# R211.net
KiCad netlist of a schematic drawn in EAGLE
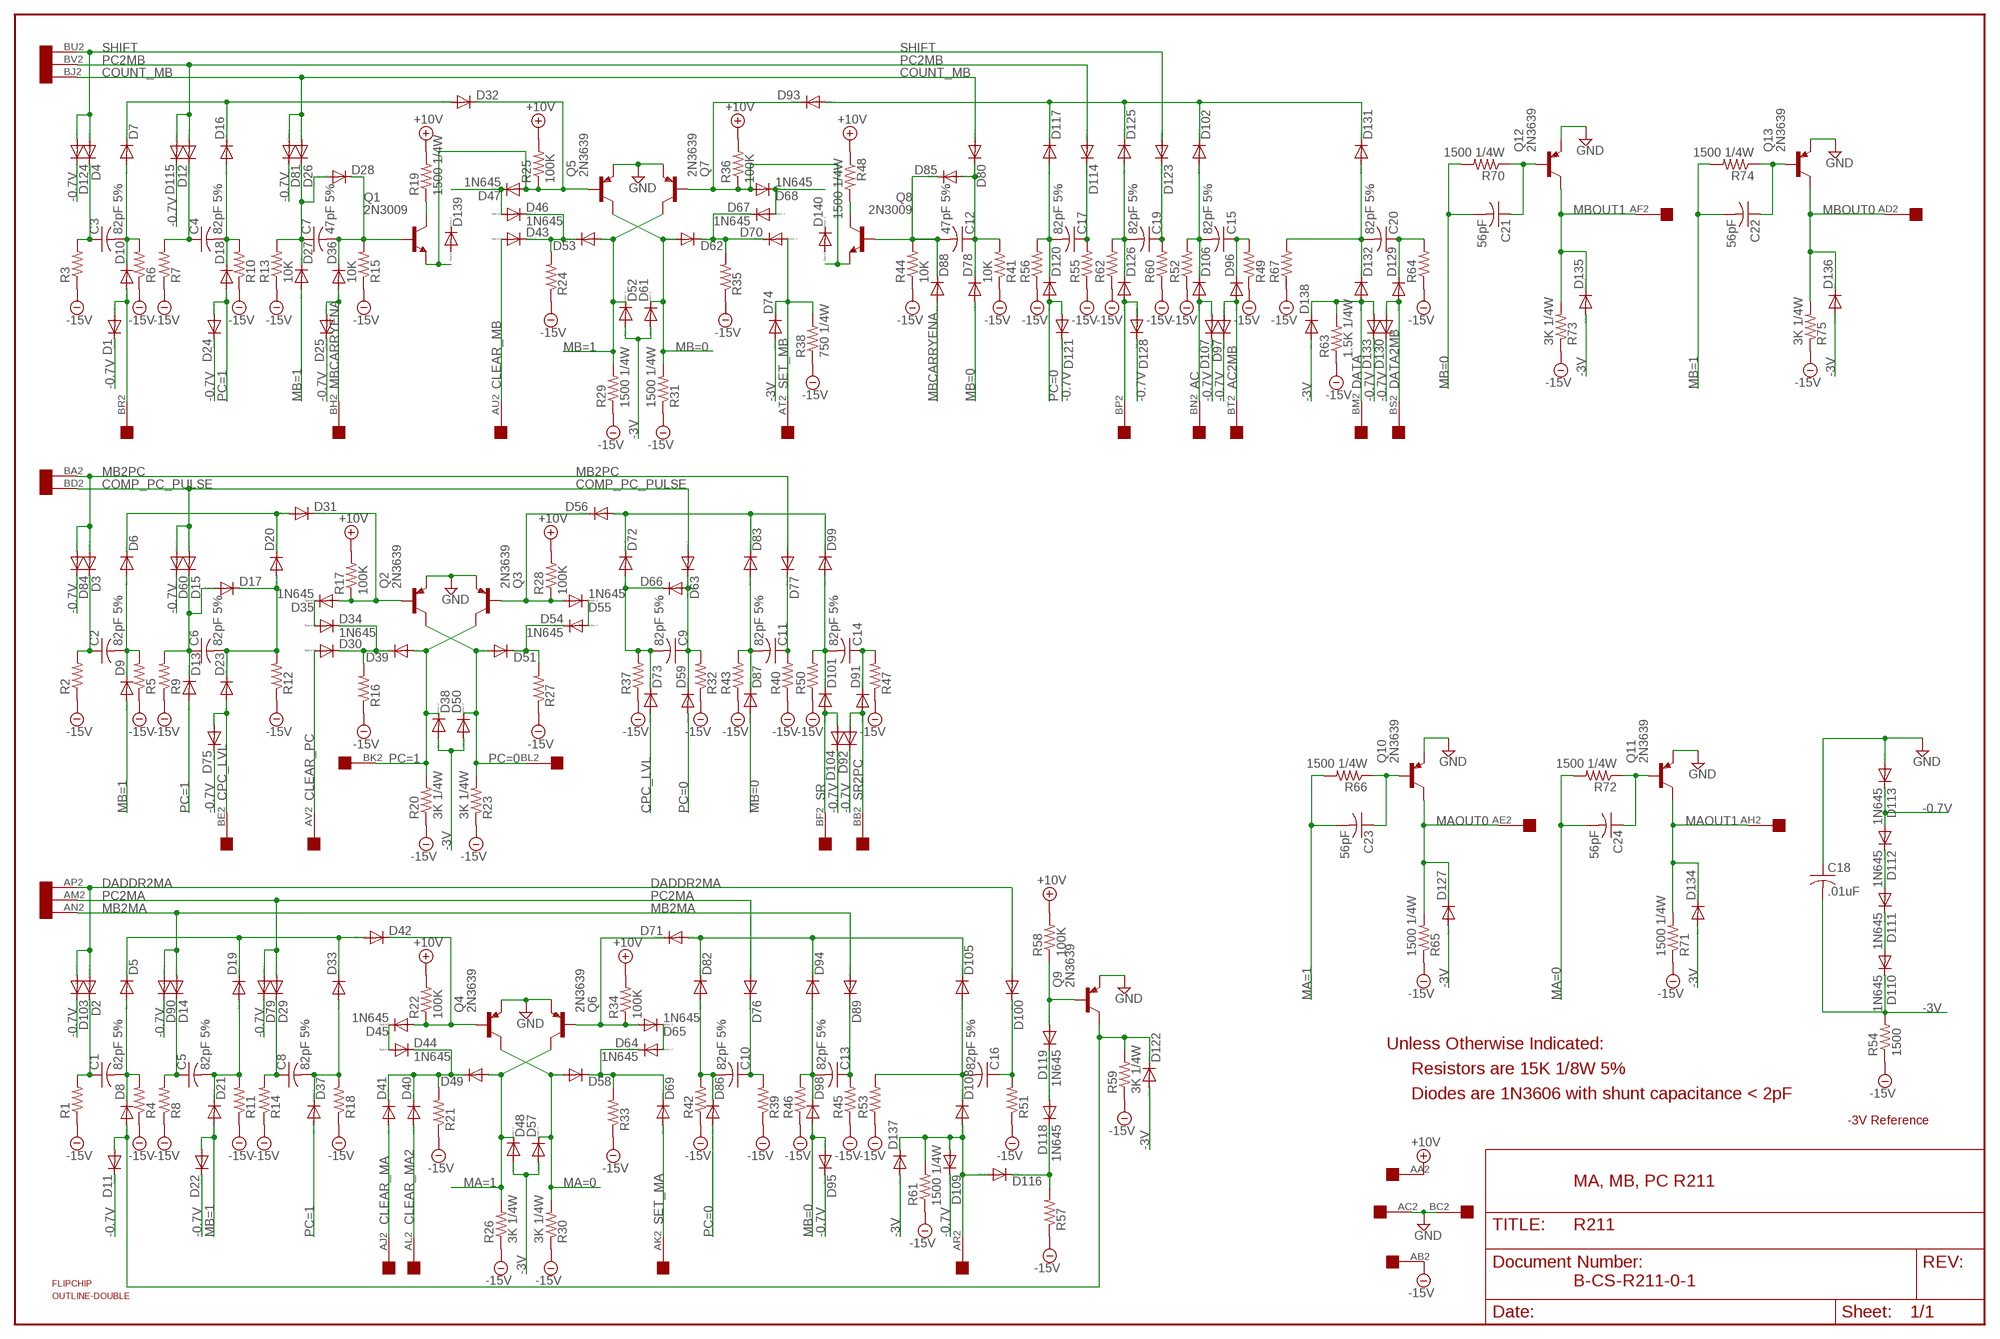
[diagram p0: schematic, sheet 1]

(export (version "E")
  (design (tool "Eeschema 10.0.6"))
  (components
    (comp (ref "C1")
      (value "82pF 5%")
      (footprint "eagle-import:C050-025X075")
      (libsource (lib "eagle-import") (part "C-US050-025X075"))
    )
    (comp (ref "C2")
      (value "82pF 5%")
      (footprint "eagle-import:C050-025X075")
      (libsource (lib "eagle-import") (part "C-US050-025X075"))
    )
    (comp (ref "C3")
      (value "82pF 5%")
      (footprint "eagle-import:C050-025X075")
      (libsource (lib "eagle-import") (part "C-US050-025X075"))
    )
    (comp (ref "C4")
      (value "82pF 5%")
      (footprint "eagle-import:C050-025X075")
      (libsource (lib "eagle-import") (part "C-US050-025X075"))
    )
    (comp (ref "C5")
      (value "82pF 5%")
      (footprint "eagle-import:C050-025X075")
      (libsource (lib "eagle-import") (part "C-US050-025X075"))
    )
    (comp (ref "C6")
      (value "82pF 5%")
      (footprint "eagle-import:C050-025X075")
      (libsource (lib "eagle-import") (part "C-US050-025X075"))
    )
    (comp (ref "C7")
      (value "47pF 5%")
      (footprint "eagle-import:C050-025X075")
      (libsource (lib "eagle-import") (part "C-US050-025X075"))
    )
    (comp (ref "C8")
      (value "82pF 5%")
      (footprint "eagle-import:C050-025X075")
      (libsource (lib "eagle-import") (part "C-US050-025X075"))
    )
    (comp (ref "C9")
      (value "82pF 5%")
      (footprint "eagle-import:C050-025X075")
      (libsource (lib "eagle-import") (part "C-US050-025X075"))
    )
    (comp (ref "C10")
      (value "82pF 5%")
      (footprint "eagle-import:C050-025X075")
      (libsource (lib "eagle-import") (part "C-US050-025X075"))
    )
    (comp (ref "C11")
      (value "82pF 5%")
      (footprint "eagle-import:C050-025X075")
      (libsource (lib "eagle-import") (part "C-US050-025X075"))
    )
    (comp (ref "C12")
      (value "47pF 5%")
      (footprint "eagle-import:C050-025X075")
      (libsource (lib "eagle-import") (part "C-US050-025X075"))
    )
    (comp (ref "C13")
      (value "82pF 5%")
      (footprint "eagle-import:C050-025X075")
      (libsource (lib "eagle-import") (part "C-US050-025X075"))
    )
    (comp (ref "C14")
      (value "82pF 5%")
      (footprint "eagle-import:C050-025X075")
      (libsource (lib "eagle-import") (part "C-US050-025X075"))
    )
    (comp (ref "C15")
      (value "82pF 5%")
      (footprint "eagle-import:C050-025X075")
      (libsource (lib "eagle-import") (part "C-US050-025X075"))
    )
    (comp (ref "C16")
      (value "82pF 5%")
      (footprint "eagle-import:C050-025X075")
      (libsource (lib "eagle-import") (part "C-US050-025X075"))
    )
    (comp (ref "C17")
      (value "82pF 5%")
      (footprint "eagle-import:C050-025X075")
      (libsource (lib "eagle-import") (part "C-US050-025X075"))
    )
    (comp (ref "C18")
      (value ".01uF")
      (footprint "eagle-import:C050-025X075")
      (libsource (lib "eagle-import") (part "C-US050-025X075"))
    )
    (comp (ref "C19")
      (value "82pF 5%")
      (footprint "eagle-import:C050-025X075")
      (libsource (lib "eagle-import") (part "C-US050-025X075"))
    )
    (comp (ref "C20")
      (value "82pF 5%")
      (footprint "eagle-import:C050-025X075")
      (libsource (lib "eagle-import") (part "C-US050-025X075"))
    )
    (comp (ref "C21")
      (value "56pF")
      (footprint "eagle-import:C050-025X075")
      (libsource (lib "eagle-import") (part "C-US050-025X075"))
    )
    (comp (ref "C22")
      (value "56pF")
      (footprint "eagle-import:C050-025X075")
      (libsource (lib "eagle-import") (part "C-US050-025X075"))
    )
    (comp (ref "C23")
      (value "56pF")
      (footprint "eagle-import:C050-025X075")
      (libsource (lib "eagle-import") (part "C-US050-025X075"))
    )
    (comp (ref "C24")
      (value "56pF")
      (footprint "eagle-import:C050-025X075")
      (libsource (lib "eagle-import") (part "C-US050-025X075"))
    )
    (comp (ref "D1")
      (value "1N4148DO35-10")
      (footprint "eagle-import:DO35-10")
      (libsource (lib "eagle-import") (part "1N4148DO35-10"))
    )
    (comp (ref "D2")
      (value "1N4148DO35-10")
      (footprint "eagle-import:DO35-10")
      (libsource (lib "eagle-import") (part "1N4148DO35-10"))
    )
    (comp (ref "D3")
      (value "1N4148DO35-10")
      (footprint "eagle-import:DO35-10")
      (libsource (lib "eagle-import") (part "1N4148DO35-10"))
    )
    (comp (ref "D4")
      (value "1N4148DO35-10")
      (footprint "eagle-import:DO35-10")
      (libsource (lib "eagle-import") (part "1N4148DO35-10"))
    )
    (comp (ref "D5")
      (value "1N4148DO35-10")
      (footprint "eagle-import:DO35-10")
      (libsource (lib "eagle-import") (part "1N4148DO35-10"))
    )
    (comp (ref "D6")
      (value "1N4148DO35-10")
      (footprint "eagle-import:DO35-10")
      (libsource (lib "eagle-import") (part "1N4148DO35-10"))
    )
    (comp (ref "D7")
      (value "1N4148DO35-10")
      (footprint "eagle-import:DO35-10")
      (libsource (lib "eagle-import") (part "1N4148DO35-10"))
    )
    (comp (ref "D8")
      (value "1N4148DO35-10")
      (footprint "eagle-import:DO35-10")
      (libsource (lib "eagle-import") (part "1N4148DO35-10"))
    )
    (comp (ref "D9")
      (value "1N4148DO35-10")
      (footprint "eagle-import:DO35-10")
      (libsource (lib "eagle-import") (part "1N4148DO35-10"))
    )
    (comp (ref "D10")
      (value "1N4148DO35-10")
      (footprint "eagle-import:DO35-10")
      (libsource (lib "eagle-import") (part "1N4148DO35-10"))
    )
    (comp (ref "D11")
      (value "1N4148DO35-10")
      (footprint "eagle-import:DO35-10")
      (libsource (lib "eagle-import") (part "1N4148DO35-10"))
    )
    (comp (ref "D12")
      (value "1N4148DO35-10")
      (footprint "eagle-import:DO35-10")
      (libsource (lib "eagle-import") (part "1N4148DO35-10"))
    )
    (comp (ref "D13")
      (value "1N4148DO35-10")
      (footprint "eagle-import:DO35-10")
      (libsource (lib "eagle-import") (part "1N4148DO35-10"))
    )
    (comp (ref "D14")
      (value "1N4148DO35-10")
      (footprint "eagle-import:DO35-10")
      (libsource (lib "eagle-import") (part "1N4148DO35-10"))
    )
    (comp (ref "D15")
      (value "1N4148DO35-10")
      (footprint "eagle-import:DO35-10")
      (libsource (lib "eagle-import") (part "1N4148DO35-10"))
    )
    (comp (ref "D16")
      (value "1N4148DO35-10")
      (footprint "eagle-import:DO35-10")
      (libsource (lib "eagle-import") (part "1N4148DO35-10"))
    )
    (comp (ref "D17")
      (value "1N4148DO35-10")
      (footprint "eagle-import:DO35-10")
      (libsource (lib "eagle-import") (part "1N4148DO35-10"))
    )
    (comp (ref "D18")
      (value "1N4148DO35-10")
      (footprint "eagle-import:DO35-10")
      (libsource (lib "eagle-import") (part "1N4148DO35-10"))
    )
    (comp (ref "D19")
      (value "1N4148DO35-10")
      (footprint "eagle-import:DO35-10")
      (libsource (lib "eagle-import") (part "1N4148DO35-10"))
    )
    (comp (ref "D20")
      (value "1N4148DO35-10")
      (footprint "eagle-import:DO35-10")
      (libsource (lib "eagle-import") (part "1N4148DO35-10"))
    )
    (comp (ref "D21")
      (value "1N4148DO35-10")
      (footprint "eagle-import:DO35-10")
      (libsource (lib "eagle-import") (part "1N4148DO35-10"))
    )
    (comp (ref "D22")
      (value "1N4148DO35-10")
      (footprint "eagle-import:DO35-10")
      (libsource (lib "eagle-import") (part "1N4148DO35-10"))
    )
    (comp (ref "D23")
      (value "1N4148DO35-10")
      (footprint "eagle-import:DO35-10")
      (libsource (lib "eagle-import") (part "1N4148DO35-10"))
    )
    (comp (ref "D24")
      (value "1N4148DO35-10")
      (footprint "eagle-import:DO35-10")
      (libsource (lib "eagle-import") (part "1N4148DO35-10"))
    )
    (comp (ref "D25")
      (value "1N4148DO35-10")
      (footprint "eagle-import:DO35-10")
      (libsource (lib "eagle-import") (part "1N4148DO35-10"))
    )
    (comp (ref "D26")
      (value "1N4148DO35-10")
      (footprint "eagle-import:DO35-10")
      (libsource (lib "eagle-import") (part "1N4148DO35-10"))
    )
    (comp (ref "D27")
      (value "1N4148DO35-10")
      (footprint "eagle-import:DO35-10")
      (libsource (lib "eagle-import") (part "1N4148DO35-10"))
    )
    (comp (ref "D28")
      (value "1N4148DO35-10")
      (footprint "eagle-import:DO35-10")
      (libsource (lib "eagle-import") (part "1N4148DO35-10"))
    )
    (comp (ref "D29")
      (value "1N4148DO35-10")
      (footprint "eagle-import:DO35-10")
      (libsource (lib "eagle-import") (part "1N4148DO35-10"))
    )
    (comp (ref "D30")
      (value "1N4148DO35-10")
      (footprint "eagle-import:DO35-10")
      (libsource (lib "eagle-import") (part "1N4148DO35-10"))
    )
    (comp (ref "D31")
      (value "1N4148DO35-10")
      (footprint "eagle-import:DO35-10")
      (libsource (lib "eagle-import") (part "1N4148DO35-10"))
    )
    (comp (ref "D32")
      (value "1N4148DO35-10")
      (footprint "eagle-import:DO35-10")
      (libsource (lib "eagle-import") (part "1N4148DO35-10"))
    )
    (comp (ref "D33")
      (value "1N4148DO35-10")
      (footprint "eagle-import:DO35-10")
      (libsource (lib "eagle-import") (part "1N4148DO35-10"))
    )
    (comp (ref "D34")
      (value "1N645")
      (footprint "eagle-import:DO35-10")
      (libsource (lib "eagle-import") (part "1N4148DO35-10"))
    )
    (comp (ref "D35")
      (value "1N645")
      (footprint "eagle-import:DO35-10")
      (libsource (lib "eagle-import") (part "1N4148DO35-10"))
    )
    (comp (ref "D36")
      (value "1N4148DO35-10")
      (footprint "eagle-import:DO35-10")
      (libsource (lib "eagle-import") (part "1N4148DO35-10"))
    )
    (comp (ref "D37")
      (value "1N4148DO35-10")
      (footprint "eagle-import:DO35-10")
      (libsource (lib "eagle-import") (part "1N4148DO35-10"))
    )
    (comp (ref "D38")
      (value "1N4148DO35-10")
      (footprint "eagle-import:DO35-10")
      (libsource (lib "eagle-import") (part "1N4148DO35-10"))
    )
    (comp (ref "D39")
      (value "1N4148DO35-10")
      (footprint "eagle-import:DO35-10")
      (libsource (lib "eagle-import") (part "1N4148DO35-10"))
    )
    (comp (ref "D40")
      (value "1N4148DO35-10")
      (footprint "eagle-import:DO35-10")
      (libsource (lib "eagle-import") (part "1N4148DO35-10"))
    )
    (comp (ref "D41")
      (value "1N4148DO35-10")
      (footprint "eagle-import:DO35-10")
      (libsource (lib "eagle-import") (part "1N4148DO35-10"))
    )
    (comp (ref "D42")
      (value "1N4148DO35-10")
      (footprint "eagle-import:DO35-10")
      (libsource (lib "eagle-import") (part "1N4148DO35-10"))
    )
    (comp (ref "D43")
      (value "1N4148DO35-10")
      (footprint "eagle-import:DO35-10")
      (libsource (lib "eagle-import") (part "1N4148DO35-10"))
    )
    (comp (ref "D44")
      (value "1N645")
      (footprint "eagle-import:DO35-10")
      (libsource (lib "eagle-import") (part "1N4148DO35-10"))
    )
    (comp (ref "D45")
      (value "1N645")
      (footprint "eagle-import:DO35-10")
      (libsource (lib "eagle-import") (part "1N4148DO35-10"))
    )
    (comp (ref "D46")
      (value "1N645")
      (footprint "eagle-import:DO35-10")
      (libsource (lib "eagle-import") (part "1N4148DO35-10"))
    )
    (comp (ref "D47")
      (value "1N645")
      (footprint "eagle-import:DO35-10")
      (libsource (lib "eagle-import") (part "1N4148DO35-10"))
    )
    (comp (ref "D48")
      (value "1N4148DO35-10")
      (footprint "eagle-import:DO35-10")
      (libsource (lib "eagle-import") (part "1N4148DO35-10"))
    )
    (comp (ref "D49")
      (value "1N4148DO35-10")
      (footprint "eagle-import:DO35-10")
      (libsource (lib "eagle-import") (part "1N4148DO35-10"))
    )
    (comp (ref "D50")
      (value "1N4148DO35-10")
      (footprint "eagle-import:DO35-10")
      (libsource (lib "eagle-import") (part "1N4148DO35-10"))
    )
    (comp (ref "D51")
      (value "1N4148DO35-10")
      (footprint "eagle-import:DO35-10")
      (libsource (lib "eagle-import") (part "1N4148DO35-10"))
    )
    (comp (ref "D52")
      (value "1N4148DO35-10")
      (footprint "eagle-import:DO35-10")
      (libsource (lib "eagle-import") (part "1N4148DO35-10"))
    )
    (comp (ref "D53")
      (value "1N4148DO35-10")
      (footprint "eagle-import:DO35-10")
      (libsource (lib "eagle-import") (part "1N4148DO35-10"))
    )
    (comp (ref "D54")
      (value "1N645")
      (footprint "eagle-import:DO35-10")
      (libsource (lib "eagle-import") (part "1N4148DO35-10"))
    )
    (comp (ref "D55")
      (value "1N645")
      (footprint "eagle-import:DO35-10")
      (libsource (lib "eagle-import") (part "1N4148DO35-10"))
    )
    (comp (ref "D56")
      (value "1N4148DO35-10")
      (footprint "eagle-import:DO35-10")
      (libsource (lib "eagle-import") (part "1N4148DO35-10"))
    )
    (comp (ref "D57")
      (value "1N4148DO35-10")
      (footprint "eagle-import:DO35-10")
      (libsource (lib "eagle-import") (part "1N4148DO35-10"))
    )
    (comp (ref "D58")
      (value "1N4148DO35-10")
      (footprint "eagle-import:DO35-10")
      (libsource (lib "eagle-import") (part "1N4148DO35-10"))
    )
    (comp (ref "D59")
      (value "1N4148DO35-10")
      (footprint "eagle-import:DO35-10")
      (libsource (lib "eagle-import") (part "1N4148DO35-10"))
    )
    (comp (ref "D60")
      (value "1N4148DO35-10")
      (footprint "eagle-import:DO35-10")
      (libsource (lib "eagle-import") (part "1N4148DO35-10"))
    )
    (comp (ref "D61")
      (value "1N4148DO35-10")
      (footprint "eagle-import:DO35-10")
      (libsource (lib "eagle-import") (part "1N4148DO35-10"))
    )
    (comp (ref "D62")
      (value "1N4148DO35-10")
      (footprint "eagle-import:DO35-10")
      (libsource (lib "eagle-import") (part "1N4148DO35-10"))
    )
    (comp (ref "D63")
      (value "1N4148DO35-10")
      (footprint "eagle-import:DO35-10")
      (libsource (lib "eagle-import") (part "1N4148DO35-10"))
    )
    (comp (ref "D64")
      (value "1N645")
      (footprint "eagle-import:DO35-10")
      (libsource (lib "eagle-import") (part "1N4148DO35-10"))
    )
    (comp (ref "D65")
      (value "1N645")
      (footprint "eagle-import:DO35-10")
      (libsource (lib "eagle-import") (part "1N4148DO35-10"))
    )
    (comp (ref "D66")
      (value "1N4148DO35-10")
      (footprint "eagle-import:DO35-10")
      (libsource (lib "eagle-import") (part "1N4148DO35-10"))
    )
    (comp (ref "D67")
      (value "1N645")
      (footprint "eagle-import:DO35-10")
      (libsource (lib "eagle-import") (part "1N4148DO35-10"))
    )
    (comp (ref "D68")
      (value "1N645")
      (footprint "eagle-import:DO35-10")
      (libsource (lib "eagle-import") (part "1N4148DO35-10"))
    )
    (comp (ref "D69")
      (value "1N4148DO35-10")
      (footprint "eagle-import:DO35-10")
      (libsource (lib "eagle-import") (part "1N4148DO35-10"))
    )
    (comp (ref "D70")
      (value "1N4148DO35-10")
      (footprint "eagle-import:DO35-10")
      (libsource (lib "eagle-import") (part "1N4148DO35-10"))
    )
    (comp (ref "D71")
      (value "1N4148DO35-10")
      (footprint "eagle-import:DO35-10")
      (libsource (lib "eagle-import") (part "1N4148DO35-10"))
    )
    (comp (ref "D72")
      (value "1N4148DO35-10")
      (footprint "eagle-import:DO35-10")
      (libsource (lib "eagle-import") (part "1N4148DO35-10"))
    )
    (comp (ref "D73")
      (value "1N4148DO35-10")
      (footprint "eagle-import:DO35-10")
      (libsource (lib "eagle-import") (part "1N4148DO35-10"))
    )
    (comp (ref "D74")
      (value "1N4148DO35-10")
      (footprint "eagle-import:DO35-10")
      (libsource (lib "eagle-import") (part "1N4148DO35-10"))
    )
    (comp (ref "D75")
      (value "1N4148DO35-10")
      (footprint "eagle-import:DO35-10")
      (libsource (lib "eagle-import") (part "1N4148DO35-10"))
    )
    (comp (ref "D76")
      (value "1N4148DO35-10")
      (footprint "eagle-import:DO35-10")
      (libsource (lib "eagle-import") (part "1N4148DO35-10"))
    )
    (comp (ref "D77")
      (value "1N4148DO35-10")
      (footprint "eagle-import:DO35-10")
      (libsource (lib "eagle-import") (part "1N4148DO35-10"))
    )
    (comp (ref "D78")
      (value "1N4148DO35-10")
      (footprint "eagle-import:DO35-10")
      (libsource (lib "eagle-import") (part "1N4148DO35-10"))
    )
    (comp (ref "D79")
      (value "1N4148DO35-10")
      (footprint "eagle-import:DO35-10")
      (libsource (lib "eagle-import") (part "1N4148DO35-10"))
    )
    (comp (ref "D80")
      (value "1N4148DO35-10")
      (footprint "eagle-import:DO35-10")
      (libsource (lib "eagle-import") (part "1N4148DO35-10"))
    )
    (comp (ref "D81")
      (value "1N4148DO35-10")
      (footprint "eagle-import:DO35-10")
      (libsource (lib "eagle-import") (part "1N4148DO35-10"))
    )
    (comp (ref "D82")
      (value "1N4148DO35-10")
      (footprint "eagle-import:DO35-10")
      (libsource (lib "eagle-import") (part "1N4148DO35-10"))
    )
    (comp (ref "D83")
      (value "1N4148DO35-10")
      (footprint "eagle-import:DO35-10")
      (libsource (lib "eagle-import") (part "1N4148DO35-10"))
    )
    (comp (ref "D84")
      (value "1N4148DO35-10")
      (footprint "eagle-import:DO35-10")
      (libsource (lib "eagle-import") (part "1N4148DO35-10"))
    )
    (comp (ref "D85")
      (value "1N4148DO35-10")
      (footprint "eagle-import:DO35-10")
      (libsource (lib "eagle-import") (part "1N4148DO35-10"))
    )
    (comp (ref "D86")
      (value "1N4148DO35-10")
      (footprint "eagle-import:DO35-10")
      (libsource (lib "eagle-import") (part "1N4148DO35-10"))
    )
    (comp (ref "D87")
      (value "1N4148DO35-10")
      (footprint "eagle-import:DO35-10")
      (libsource (lib "eagle-import") (part "1N4148DO35-10"))
    )
    (comp (ref "D88")
      (value "1N4148DO35-10")
      (footprint "eagle-import:DO35-10")
      (libsource (lib "eagle-import") (part "1N4148DO35-10"))
    )
    (comp (ref "D89")
      (value "1N4148DO35-10")
      (footprint "eagle-import:DO35-10")
      (libsource (lib "eagle-import") (part "1N4148DO35-10"))
    )
    (comp (ref "D90")
      (value "1N4148DO35-10")
      (footprint "eagle-import:DO35-10")
      (libsource (lib "eagle-import") (part "1N4148DO35-10"))
    )
    (comp (ref "D91")
      (value "1N4148DO35-10")
      (footprint "eagle-import:DO35-10")
      (libsource (lib "eagle-import") (part "1N4148DO35-10"))
    )
    (comp (ref "D92")
      (value "1N4148DO35-10")
      (footprint "eagle-import:DO35-10")
      (libsource (lib "eagle-import") (part "1N4148DO35-10"))
    )
    (comp (ref "D93")
      (value "1N4148DO35-10")
      (footprint "eagle-import:DO35-10")
      (libsource (lib "eagle-import") (part "1N4148DO35-10"))
    )
    (comp (ref "D94")
      (value "1N4148DO35-10")
      (footprint "eagle-import:DO35-10")
      (libsource (lib "eagle-import") (part "1N4148DO35-10"))
    )
    (comp (ref "D95")
      (value "1N4148DO35-10")
      (footprint "eagle-import:DO35-10")
      (libsource (lib "eagle-import") (part "1N4148DO35-10"))
    )
    (comp (ref "D96")
      (value "1N4148DO35-10")
      (footprint "eagle-import:DO35-10")
      (libsource (lib "eagle-import") (part "1N4148DO35-10"))
    )
    (comp (ref "D97")
      (value "1N4148DO35-10")
      (footprint "eagle-import:DO35-10")
      (libsource (lib "eagle-import") (part "1N4148DO35-10"))
    )
    (comp (ref "D98")
      (value "1N4148DO35-10")
      (footprint "eagle-import:DO35-10")
      (libsource (lib "eagle-import") (part "1N4148DO35-10"))
    )
    (comp (ref "D99")
      (value "1N4148DO35-10")
      (footprint "eagle-import:DO35-10")
      (libsource (lib "eagle-import") (part "1N4148DO35-10"))
    )
    (comp (ref "D100")
      (value "1N4148DO35-10")
      (footprint "eagle-import:DO35-10")
      (libsource (lib "eagle-import") (part "1N4148DO35-10"))
    )
    (comp (ref "D101")
      (value "1N4148DO35-10")
      (footprint "eagle-import:DO35-10")
      (libsource (lib "eagle-import") (part "1N4148DO35-10"))
    )
    (comp (ref "D102")
      (value "1N4148DO35-10")
      (footprint "eagle-import:DO35-10")
      (libsource (lib "eagle-import") (part "1N4148DO35-10"))
    )
    (comp (ref "D103")
      (value "1N4148DO35-10")
      (footprint "eagle-import:DO35-10")
      (libsource (lib "eagle-import") (part "1N4148DO35-10"))
    )
    (comp (ref "D104")
      (value "1N4148DO35-10")
      (footprint "eagle-import:DO35-10")
      (libsource (lib "eagle-import") (part "1N4148DO35-10"))
    )
    (comp (ref "D105")
      (value "1N4148DO35-10")
      (footprint "eagle-import:DO35-10")
      (libsource (lib "eagle-import") (part "1N4148DO35-10"))
    )
    (comp (ref "D106")
      (value "1N4148DO35-10")
      (footprint "eagle-import:DO35-10")
      (libsource (lib "eagle-import") (part "1N4148DO35-10"))
    )
    (comp (ref "D107")
      (value "1N4148DO35-10")
      (footprint "eagle-import:DO35-10")
      (libsource (lib "eagle-import") (part "1N4148DO35-10"))
    )
    (comp (ref "D108")
      (value "1N4148DO35-10")
      (footprint "eagle-import:DO35-10")
      (libsource (lib "eagle-import") (part "1N4148DO35-10"))
    )
    (comp (ref "D109")
      (value "1N4148DO35-10")
      (footprint "eagle-import:DO35-10")
      (libsource (lib "eagle-import") (part "1N4148DO35-10"))
    )
    (comp (ref "D110")
      (value "1N645")
      (footprint "eagle-import:DO35-10")
      (libsource (lib "eagle-import") (part "1N4148DO35-10"))
    )
    (comp (ref "D111")
      (value "1N645")
      (footprint "eagle-import:DO35-10")
      (libsource (lib "eagle-import") (part "1N4148DO35-10"))
    )
    (comp (ref "D112")
      (value "1N645")
      (footprint "eagle-import:DO35-10")
      (libsource (lib "eagle-import") (part "1N4148DO35-10"))
    )
    (comp (ref "D113")
      (value "1N645")
      (footprint "eagle-import:DO35-10")
      (libsource (lib "eagle-import") (part "1N4148DO35-10"))
    )
    (comp (ref "D114")
      (value "1N4148DO35-10")
      (footprint "eagle-import:DO35-10")
      (libsource (lib "eagle-import") (part "1N4148DO35-10"))
    )
    (comp (ref "D115")
      (value "1N4148DO35-10")
      (footprint "eagle-import:DO35-10")
      (libsource (lib "eagle-import") (part "1N4148DO35-10"))
    )
    (comp (ref "D116")
      (value "1N4148DO35-10")
      (footprint "eagle-import:DO35-10")
      (libsource (lib "eagle-import") (part "1N4148DO35-10"))
    )
    (comp (ref "D117")
      (value "1N4148DO35-10")
      (footprint "eagle-import:DO35-10")
      (libsource (lib "eagle-import") (part "1N4148DO35-10"))
    )
    (comp (ref "D118")
      (value "1N645")
      (footprint "eagle-import:DO35-10")
      (libsource (lib "eagle-import") (part "1N4148DO35-10"))
    )
    (comp (ref "D119")
      (value "1N645")
      (footprint "eagle-import:DO35-10")
      (libsource (lib "eagle-import") (part "1N4148DO35-10"))
    )
    (comp (ref "D120")
      (value "1N4148DO35-10")
      (footprint "eagle-import:DO35-10")
      (libsource (lib "eagle-import") (part "1N4148DO35-10"))
    )
    (comp (ref "D121")
      (value "1N4148DO35-10")
      (footprint "eagle-import:DO35-10")
      (libsource (lib "eagle-import") (part "1N4148DO35-10"))
    )
    (comp (ref "D122")
      (value "1N4148DO35-10")
      (footprint "eagle-import:DO35-10")
      (libsource (lib "eagle-import") (part "1N4148DO35-10"))
    )
    (comp (ref "D123")
      (value "1N4148DO35-10")
      (footprint "eagle-import:DO35-10")
      (libsource (lib "eagle-import") (part "1N4148DO35-10"))
    )
    (comp (ref "D124")
      (value "1N4148DO35-10")
      (footprint "eagle-import:DO35-10")
      (libsource (lib "eagle-import") (part "1N4148DO35-10"))
    )
    (comp (ref "D125")
      (value "1N4148DO35-10")
      (footprint "eagle-import:DO35-10")
      (libsource (lib "eagle-import") (part "1N4148DO35-10"))
    )
    (comp (ref "D126")
      (value "1N4148DO35-10")
      (footprint "eagle-import:DO35-10")
      (libsource (lib "eagle-import") (part "1N4148DO35-10"))
    )
    (comp (ref "D127")
      (value "1N4148DO35-10")
      (footprint "eagle-import:DO35-10")
      (libsource (lib "eagle-import") (part "1N4148DO35-10"))
    )
    (comp (ref "D128")
      (value "1N4148DO35-10")
      (footprint "eagle-import:DO35-10")
      (libsource (lib "eagle-import") (part "1N4148DO35-10"))
    )
    (comp (ref "D129")
      (value "1N4148DO35-10")
      (footprint "eagle-import:DO35-10")
      (libsource (lib "eagle-import") (part "1N4148DO35-10"))
    )
    (comp (ref "D130")
      (value "1N4148DO35-10")
      (footprint "eagle-import:DO35-10")
      (libsource (lib "eagle-import") (part "1N4148DO35-10"))
    )
    (comp (ref "D131")
      (value "1N4148DO35-10")
      (footprint "eagle-import:DO35-10")
      (libsource (lib "eagle-import") (part "1N4148DO35-10"))
    )
    (comp (ref "D132")
      (value "1N4148DO35-10")
      (footprint "eagle-import:DO35-10")
      (libsource (lib "eagle-import") (part "1N4148DO35-10"))
    )
    (comp (ref "D133")
      (value "1N4148DO35-10")
      (footprint "eagle-import:DO35-10")
      (libsource (lib "eagle-import") (part "1N4148DO35-10"))
    )
    (comp (ref "D134")
      (value "1N4148DO35-10")
      (footprint "eagle-import:DO35-10")
      (libsource (lib "eagle-import") (part "1N4148DO35-10"))
    )
    (comp (ref "D135")
      (value "1N4148DO35-10")
      (footprint "eagle-import:DO35-10")
      (libsource (lib "eagle-import") (part "1N4148DO35-10"))
    )
    (comp (ref "D136")
      (value "1N4148DO35-10")
      (footprint "eagle-import:DO35-10")
      (libsource (lib "eagle-import") (part "1N4148DO35-10"))
    )
    (comp (ref "D137")
      (value "1N4148DO35-10")
      (footprint "eagle-import:DO35-10")
      (libsource (lib "eagle-import") (part "1N4148DO35-10"))
    )
    (comp (ref "D138")
      (value "1N4148DO35-10")
      (footprint "eagle-import:DO35-10")
      (libsource (lib "eagle-import") (part "1N4148DO35-10"))
    )
    (comp (ref "D139")
      (value "1N4148DO35-10")
      (footprint "eagle-import:DO35-10")
      (libsource (lib "eagle-import") (part "1N4148DO35-10"))
    )
    (comp (ref "D140")
      (value "1N4148DO35-10")
      (footprint "eagle-import:DO35-10")
      (libsource (lib "eagle-import") (part "1N4148DO35-10"))
    )
    (comp (ref "Q1")
      (value "2N3009")
      (footprint "eagle-import:TO5")
      (libsource (lib "eagle-import") (part "2N2102"))
    )
    (comp (ref "Q2")
      (value "2N3639")
      (footprint "eagle-import:TO39")
      (libsource (lib "eagle-import") (part "2N3637"))
    )
    (comp (ref "Q3")
      (value "2N3639")
      (footprint "eagle-import:TO39")
      (libsource (lib "eagle-import") (part "2N3637"))
    )
    (comp (ref "Q4")
      (value "2N3639")
      (footprint "eagle-import:TO39")
      (libsource (lib "eagle-import") (part "2N3637"))
    )
    (comp (ref "Q5")
      (value "2N3639")
      (footprint "eagle-import:TO39")
      (libsource (lib "eagle-import") (part "2N3637"))
    )
    (comp (ref "Q6")
      (value "2N3639")
      (footprint "eagle-import:TO39")
      (libsource (lib "eagle-import") (part "2N3637"))
    )
    (comp (ref "Q7")
      (value "2N3639")
      (footprint "eagle-import:TO39")
      (libsource (lib "eagle-import") (part "2N3637"))
    )
    (comp (ref "Q8")
      (value "2N3009")
      (footprint "eagle-import:TO5")
      (libsource (lib "eagle-import") (part "2N2102"))
    )
    (comp (ref "Q9")
      (value "2N3639")
      (footprint "eagle-import:TO39")
      (libsource (lib "eagle-import") (part "2N3637"))
    )
    (comp (ref "Q10")
      (value "2N3639")
      (footprint "eagle-import:TO39")
      (libsource (lib "eagle-import") (part "2N3637"))
    )
    (comp (ref "Q11")
      (value "2N3639")
      (footprint "eagle-import:TO39")
      (libsource (lib "eagle-import") (part "2N3637"))
    )
    (comp (ref "Q12")
      (value "2N3639")
      (footprint "eagle-import:TO39")
      (libsource (lib "eagle-import") (part "2N3637"))
    )
    (comp (ref "Q13")
      (value "2N3639")
      (footprint "eagle-import:TO39")
      (libsource (lib "eagle-import") (part "2N3637"))
    )
    (comp (ref "R1")
      (value "R-US_0207/10")
      (footprint "eagle-import:0207_10")
      (libsource (lib "eagle-import") (part "R-US_0207/10"))
    )
    (comp (ref "R2")
      (value "R-US_0207/10")
      (footprint "eagle-import:0207_10")
      (libsource (lib "eagle-import") (part "R-US_0207/10"))
    )
    (comp (ref "R3")
      (value "R-US_0207/10")
      (footprint "eagle-import:0207_10")
      (libsource (lib "eagle-import") (part "R-US_0207/10"))
    )
    (comp (ref "R4")
      (value "R-US_0207/10")
      (footprint "eagle-import:0207_10")
      (libsource (lib "eagle-import") (part "R-US_0207/10"))
    )
    (comp (ref "R5")
      (value "R-US_0207/10")
      (footprint "eagle-import:0207_10")
      (libsource (lib "eagle-import") (part "R-US_0207/10"))
    )
    (comp (ref "R6")
      (value "R-US_0207/10")
      (footprint "eagle-import:0207_10")
      (libsource (lib "eagle-import") (part "R-US_0207/10"))
    )
    (comp (ref "R7")
      (value "R-US_0207/10")
      (footprint "eagle-import:0207_10")
      (libsource (lib "eagle-import") (part "R-US_0207/10"))
    )
    (comp (ref "R8")
      (value "R-US_0207/10")
      (footprint "eagle-import:0207_10")
      (libsource (lib "eagle-import") (part "R-US_0207/10"))
    )
    (comp (ref "R9")
      (value "R-US_0207/10")
      (footprint "eagle-import:0207_10")
      (libsource (lib "eagle-import") (part "R-US_0207/10"))
    )
    (comp (ref "R10")
      (value "R-US_0207/10")
      (footprint "eagle-import:0207_10")
      (libsource (lib "eagle-import") (part "R-US_0207/10"))
    )
    (comp (ref "R11")
      (value "R-US_0207/10")
      (footprint "eagle-import:0207_10")
      (libsource (lib "eagle-import") (part "R-US_0207/10"))
    )
    (comp (ref "R12")
      (value "R-US_0207/10")
      (footprint "eagle-import:0207_10")
      (libsource (lib "eagle-import") (part "R-US_0207/10"))
    )
    (comp (ref "R13")
      (value "10K")
      (footprint "eagle-import:0207_10")
      (libsource (lib "eagle-import") (part "R-US_0207/10"))
    )
    (comp (ref "R14")
      (value "R-US_0207/10")
      (footprint "eagle-import:0207_10")
      (libsource (lib "eagle-import") (part "R-US_0207/10"))
    )
    (comp (ref "R15")
      (value "10K")
      (footprint "eagle-import:0207_10")
      (libsource (lib "eagle-import") (part "R-US_0207/10"))
    )
    (comp (ref "R16")
      (value "R-US_0207/10")
      (footprint "eagle-import:0207_10")
      (libsource (lib "eagle-import") (part "R-US_0207/10"))
    )
    (comp (ref "R17")
      (value "100K")
      (footprint "eagle-import:0207_10")
      (libsource (lib "eagle-import") (part "R-US_0207/10"))
    )
    (comp (ref "R18")
      (value "R-US_0207/10")
      (footprint "eagle-import:0207_10")
      (libsource (lib "eagle-import") (part "R-US_0207/10"))
    )
    (comp (ref "R19")
      (value "1500 1/4W")
      (footprint "eagle-import:0207_10")
      (libsource (lib "eagle-import") (part "R-US_0207/10"))
    )
    (comp (ref "R20")
      (value "3K 1/4W")
      (footprint "eagle-import:0207_10")
      (libsource (lib "eagle-import") (part "R-US_0207/10"))
    )
    (comp (ref "R21")
      (value "R-US_0207/10")
      (footprint "eagle-import:0207_10")
      (libsource (lib "eagle-import") (part "R-US_0207/10"))
    )
    (comp (ref "R22")
      (value "100K")
      (footprint "eagle-import:0207_10")
      (libsource (lib "eagle-import") (part "R-US_0207/10"))
    )
    (comp (ref "R23")
      (value "3K 1/4W")
      (footprint "eagle-import:0207_10")
      (libsource (lib "eagle-import") (part "R-US_0207/10"))
    )
    (comp (ref "R24")
      (value "R-US_0207/10")
      (footprint "eagle-import:0207_10")
      (libsource (lib "eagle-import") (part "R-US_0207/10"))
    )
    (comp (ref "R25")
      (value "100K")
      (footprint "eagle-import:0207_10")
      (libsource (lib "eagle-import") (part "R-US_0207/10"))
    )
    (comp (ref "R26")
      (value "3K 1/4W")
      (footprint "eagle-import:0207_10")
      (libsource (lib "eagle-import") (part "R-US_0207/10"))
    )
    (comp (ref "R27")
      (value "R-US_0207/10")
      (footprint "eagle-import:0207_10")
      (libsource (lib "eagle-import") (part "R-US_0207/10"))
    )
    (comp (ref "R28")
      (value "100K")
      (footprint "eagle-import:0207_10")
      (libsource (lib "eagle-import") (part "R-US_0207/10"))
    )
    (comp (ref "R29")
      (value "1500 1/4W")
      (footprint "eagle-import:0207_10")
      (libsource (lib "eagle-import") (part "R-US_0207/10"))
    )
    (comp (ref "R30")
      (value "3K 1/4W")
      (footprint "eagle-import:0207_10")
      (libsource (lib "eagle-import") (part "R-US_0207/10"))
    )
    (comp (ref "R31")
      (value "1500 1/4W")
      (footprint "eagle-import:0207_10")
      (libsource (lib "eagle-import") (part "R-US_0207/10"))
    )
    (comp (ref "R32")
      (value "R-US_0207/10")
      (footprint "eagle-import:0207_10")
      (libsource (lib "eagle-import") (part "R-US_0207/10"))
    )
    (comp (ref "R33")
      (value "R-US_0207/10")
      (footprint "eagle-import:0207_10")
      (libsource (lib "eagle-import") (part "R-US_0207/10"))
    )
    (comp (ref "R34")
      (value "100K")
      (footprint "eagle-import:0207_10")
      (libsource (lib "eagle-import") (part "R-US_0207/10"))
    )
    (comp (ref "R35")
      (value "R-US_0207/10")
      (footprint "eagle-import:0207_10")
      (libsource (lib "eagle-import") (part "R-US_0207/10"))
    )
    (comp (ref "R36")
      (value "100K")
      (footprint "eagle-import:0207_10")
      (libsource (lib "eagle-import") (part "R-US_0207/10"))
    )
    (comp (ref "R37")
      (value "R-US_0207/10")
      (footprint "eagle-import:0207_10")
      (libsource (lib "eagle-import") (part "R-US_0207/10"))
    )
    (comp (ref "R38")
      (value "750 1/4W")
      (footprint "eagle-import:0207_10")
      (libsource (lib "eagle-import") (part "R-US_0207/10"))
    )
    (comp (ref "R39")
      (value "R-US_0207/10")
      (footprint "eagle-import:0207_10")
      (libsource (lib "eagle-import") (part "R-US_0207/10"))
    )
    (comp (ref "R40")
      (value "R-US_0207/10")
      (footprint "eagle-import:0207_10")
      (libsource (lib "eagle-import") (part "R-US_0207/10"))
    )
    (comp (ref "R41")
      (value "10K")
      (footprint "eagle-import:0207_10")
      (libsource (lib "eagle-import") (part "R-US_0207/10"))
    )
    (comp (ref "R42")
      (value "R-US_0207/10")
      (footprint "eagle-import:0207_10")
      (libsource (lib "eagle-import") (part "R-US_0207/10"))
    )
    (comp (ref "R43")
      (value "R-US_0207/10")
      (footprint "eagle-import:0207_10")
      (libsource (lib "eagle-import") (part "R-US_0207/10"))
    )
    (comp (ref "R44")
      (value "10K")
      (footprint "eagle-import:0207_10")
      (libsource (lib "eagle-import") (part "R-US_0207/10"))
    )
    (comp (ref "R45")
      (value "R-US_0207/10")
      (footprint "eagle-import:0207_10")
      (libsource (lib "eagle-import") (part "R-US_0207/10"))
    )
    (comp (ref "R46")
      (value "R-US_0207/10")
      (footprint "eagle-import:0207_10")
      (libsource (lib "eagle-import") (part "R-US_0207/10"))
    )
    (comp (ref "R47")
      (value "R-US_0207/10")
      (footprint "eagle-import:0207_10")
      (libsource (lib "eagle-import") (part "R-US_0207/10"))
    )
    (comp (ref "R48")
      (value "1500 1/4W")
      (footprint "eagle-import:0207_10")
      (libsource (lib "eagle-import") (part "R-US_0207/10"))
    )
    (comp (ref "R49")
      (value "R-US_0207/10")
      (footprint "eagle-import:0207_10")
      (libsource (lib "eagle-import") (part "R-US_0207/10"))
    )
    (comp (ref "R50")
      (value "R-US_0207/10")
      (footprint "eagle-import:0207_10")
      (libsource (lib "eagle-import") (part "R-US_0207/10"))
    )
    (comp (ref "R51")
      (value "R-US_0207/10")
      (footprint "eagle-import:0207_10")
      (libsource (lib "eagle-import") (part "R-US_0207/10"))
    )
    (comp (ref "R52")
      (value "R-US_0207/10")
      (footprint "eagle-import:0207_10")
      (libsource (lib "eagle-import") (part "R-US_0207/10"))
    )
    (comp (ref "R53")
      (value "R-US_0207/10")
      (footprint "eagle-import:0207_10")
      (libsource (lib "eagle-import") (part "R-US_0207/10"))
    )
    (comp (ref "R54")
      (value "1500")
      (footprint "eagle-import:0207_10")
      (libsource (lib "eagle-import") (part "R-US_0207/10"))
    )
    (comp (ref "R55")
      (value "R-US_0207/10")
      (footprint "eagle-import:0207_10")
      (libsource (lib "eagle-import") (part "R-US_0207/10"))
    )
    (comp (ref "R56")
      (value "R-US_0207/10")
      (footprint "eagle-import:0207_10")
      (libsource (lib "eagle-import") (part "R-US_0207/10"))
    )
    (comp (ref "R57")
      (value "R-US_0207/10")
      (footprint "eagle-import:0207_10")
      (libsource (lib "eagle-import") (part "R-US_0207/10"))
    )
    (comp (ref "R58")
      (value "100K")
      (footprint "eagle-import:0207_10")
      (libsource (lib "eagle-import") (part "R-US_0207/10"))
    )
    (comp (ref "R59")
      (value "3K 1/4W")
      (footprint "eagle-import:0207_10")
      (libsource (lib "eagle-import") (part "R-US_0207/10"))
    )
    (comp (ref "R60")
      (value "R-US_0207/10")
      (footprint "eagle-import:0207_10")
      (libsource (lib "eagle-import") (part "R-US_0207/10"))
    )
    (comp (ref "R61")
      (value "1500 1/4W")
      (footprint "eagle-import:0207_10")
      (libsource (lib "eagle-import") (part "R-US_0207/10"))
    )
    (comp (ref "R62")
      (value "R-US_0207/10")
      (footprint "eagle-import:0207_10")
      (libsource (lib "eagle-import") (part "R-US_0207/10"))
    )
    (comp (ref "R63")
      (value "1.5K 1/4W")
      (footprint "eagle-import:0207_10")
      (libsource (lib "eagle-import") (part "R-US_0207/10"))
    )
    (comp (ref "R64")
      (value "R-US_0207/10")
      (footprint "eagle-import:0207_10")
      (libsource (lib "eagle-import") (part "R-US_0207/10"))
    )
    (comp (ref "R65")
      (value "1500 1/4W")
      (footprint "eagle-import:0207_10")
      (libsource (lib "eagle-import") (part "R-US_0207/10"))
    )
    (comp (ref "R66")
      (value "1500 1/4W")
      (footprint "eagle-import:0207_10")
      (libsource (lib "eagle-import") (part "R-US_0207/10"))
    )
    (comp (ref "R67")
      (value "R-US_0207/10")
      (footprint "eagle-import:0207_10")
      (libsource (lib "eagle-import") (part "R-US_0207/10"))
    )
    (comp (ref "R70")
      (value "1500 1/4W")
      (footprint "eagle-import:0207_10")
      (libsource (lib "eagle-import") (part "R-US_0207/10"))
    )
    (comp (ref "R71")
      (value "1500 1/4W")
      (footprint "eagle-import:0207_10")
      (libsource (lib "eagle-import") (part "R-US_0207/10"))
    )
    (comp (ref "R72")
      (value "1500 1/4W")
      (footprint "eagle-import:0207_10")
      (libsource (lib "eagle-import") (part "R-US_0207/10"))
    )
    (comp (ref "R73")
      (value "3K 1/4W")
      (footprint "eagle-import:0207_10")
      (libsource (lib "eagle-import") (part "R-US_0207/10"))
    )
    (comp (ref "R74")
      (value "1500 1/4W")
      (footprint "eagle-import:0207_10")
      (libsource (lib "eagle-import") (part "R-US_0207/10"))
    )
    (comp (ref "R75")
      (value "3K 1/4W")
      (footprint "eagle-import:0207_10")
      (libsource (lib "eagle-import") (part "R-US_0207/10"))
    )
    (comp (ref "U$1")
      (value "DOUBLE")
      (footprint "eagle-import:EDGE-CON4")
      (libsource (lib "eagle-import") (part "DOUBLE"))
    )
    (comp (ref "U$2")
      (value "FLIPCHIP")
      (footprint "eagle-import:FLIPCHIP")
      (libsource (lib "eagle-import") (part "FLIPCHIP"))
    )
    (comp (ref "U$3")
      (value "OUTLINE-DOUBLE")
      (footprint "eagle-import:DOUBLE")
      (libsource (lib "eagle-import") (part "OUTLINE-DOUBLE"))
    )
  )
  (nets
    (net (code "1") (name "+10V") (class "Default")
      (node (ref "R17") (pin "2") (pinfunction "2_2") (pintype "passive"))
      (node (ref "R19") (pin "2") (pinfunction "2_2") (pintype "passive"))
      (node (ref "R22") (pin "2") (pinfunction "2_2") (pintype "passive"))
      (node (ref "R25") (pin "2") (pinfunction "2_2") (pintype "passive"))
      (node (ref "R28") (pin "2") (pinfunction "2_2") (pintype "passive"))
      (node (ref "R34") (pin "2") (pinfunction "2_2") (pintype "passive"))
      (node (ref "R36") (pin "2") (pinfunction "2_2") (pintype "passive"))
      (node (ref "R48") (pin "1") (pinfunction "1_1") (pintype "passive"))
      (node (ref "R58") (pin "2") (pinfunction "2_2") (pintype "passive"))
      (node (ref "U$1") (pin "AA2") (pinfunction "1_AA2") (pintype "bidirectional"))
    )
    (net (code "2") (name "-15V") (class "Default")
      (node (ref "R1") (pin "1") (pinfunction "1_1") (pintype "passive"))
      (node (ref "R10") (pin "1") (pinfunction "1_1") (pintype "passive"))
      (node (ref "R11") (pin "1") (pinfunction "1_1") (pintype "passive"))
      (node (ref "R12") (pin "1") (pinfunction "1_1") (pintype "passive"))
      (node (ref "R13") (pin "1") (pinfunction "1_1") (pintype "passive"))
      (node (ref "R14") (pin "1") (pinfunction "1_1") (pintype "passive"))
      (node (ref "R15") (pin "1") (pinfunction "1_1") (pintype "passive"))
      (node (ref "R16") (pin "1") (pinfunction "1_1") (pintype "passive"))
      (node (ref "R18") (pin "1") (pinfunction "1_1") (pintype "passive"))
      (node (ref "R2") (pin "1") (pinfunction "1_1") (pintype "passive"))
      (node (ref "R20") (pin "1") (pinfunction "1_1") (pintype "passive"))
      (node (ref "R21") (pin "1") (pinfunction "1_1") (pintype "passive"))
      (node (ref "R23") (pin "1") (pinfunction "1_1") (pintype "passive"))
      (node (ref "R24") (pin "1") (pinfunction "1_1") (pintype "passive"))
      (node (ref "R26") (pin "1") (pinfunction "1_1") (pintype "passive"))
      (node (ref "R27") (pin "1") (pinfunction "1_1") (pintype "passive"))
      (node (ref "R29") (pin "1") (pinfunction "1_1") (pintype "passive"))
      (node (ref "R3") (pin "1") (pinfunction "1_1") (pintype "passive"))
      (node (ref "R30") (pin "1") (pinfunction "1_1") (pintype "passive"))
      (node (ref "R31") (pin "1") (pinfunction "1_1") (pintype "passive"))
      (node (ref "R32") (pin "1") (pinfunction "1_1") (pintype "passive"))
      (node (ref "R33") (pin "1") (pinfunction "1_1") (pintype "passive"))
      (node (ref "R35") (pin "1") (pinfunction "1_1") (pintype "passive"))
      (node (ref "R37") (pin "1") (pinfunction "1_1") (pintype "passive"))
      (node (ref "R38") (pin "1") (pinfunction "1_1") (pintype "passive"))
      (node (ref "R39") (pin "1") (pinfunction "1_1") (pintype "passive"))
      (node (ref "R4") (pin "1") (pinfunction "1_1") (pintype "passive"))
      (node (ref "R40") (pin "1") (pinfunction "1_1") (pintype "passive"))
      (node (ref "R41") (pin "1") (pinfunction "1_1") (pintype "passive"))
      (node (ref "R42") (pin "1") (pinfunction "1_1") (pintype "passive"))
      (node (ref "R43") (pin "1") (pinfunction "1_1") (pintype "passive"))
      (node (ref "R44") (pin "1") (pinfunction "1_1") (pintype "passive"))
      (node (ref "R45") (pin "1") (pinfunction "1_1") (pintype "passive"))
      (node (ref "R46") (pin "1") (pinfunction "1_1") (pintype "passive"))
      (node (ref "R47") (pin "1") (pinfunction "1_1") (pintype "passive"))
      (node (ref "R49") (pin "1") (pinfunction "1_1") (pintype "passive"))
      (node (ref "R5") (pin "1") (pinfunction "1_1") (pintype "passive"))
      (node (ref "R50") (pin "1") (pinfunction "1_1") (pintype "passive"))
      (node (ref "R51") (pin "1") (pinfunction "1_1") (pintype "passive"))
      (node (ref "R52") (pin "1") (pinfunction "1_1") (pintype "passive"))
      (node (ref "R53") (pin "1") (pinfunction "1_1") (pintype "passive"))
      (node (ref "R54") (pin "1") (pinfunction "1_1") (pintype "passive"))
      (node (ref "R55") (pin "1") (pinfunction "1_1") (pintype "passive"))
      (node (ref "R56") (pin "1") (pinfunction "1_1") (pintype "passive"))
      (node (ref "R57") (pin "1") (pinfunction "1_1") (pintype "passive"))
      (node (ref "R59") (pin "1") (pinfunction "1_1") (pintype "passive"))
      (node (ref "R6") (pin "1") (pinfunction "1_1") (pintype "passive"))
      (node (ref "R60") (pin "1") (pinfunction "1_1") (pintype "passive"))
      (node (ref "R61") (pin "1") (pinfunction "1_1") (pintype "passive"))
      (node (ref "R62") (pin "1") (pinfunction "1_1") (pintype "passive"))
      (node (ref "R63") (pin "1") (pinfunction "1_1") (pintype "passive"))
      (node (ref "R64") (pin "1") (pinfunction "1_1") (pintype "passive"))
      (node (ref "R65") (pin "1") (pinfunction "1_1") (pintype "passive"))
      (node (ref "R67") (pin "1") (pinfunction "1_1") (pintype "passive"))
      (node (ref "R7") (pin "1") (pinfunction "1_1") (pintype "passive"))
      (node (ref "R71") (pin "1") (pinfunction "1_1") (pintype "passive"))
      (node (ref "R73") (pin "1") (pinfunction "1_1") (pintype "passive"))
      (node (ref "R75") (pin "1") (pinfunction "1_1") (pintype "passive"))
      (node (ref "R8") (pin "1") (pinfunction "1_1") (pintype "passive"))
      (node (ref "R9") (pin "1") (pinfunction "1_1") (pintype "passive"))
      (node (ref "U$1") (pin "AB2") (pinfunction "1_AB2") (pintype "bidirectional"))
    )
    (net (code "3") (name "/-0.7V") (class "Default")
      (node (ref "D1") (pin "C") (pinfunction "C_C") (pintype "passive"))
      (node (ref "D103") (pin "C") (pinfunction "C_C") (pintype "passive"))
      (node (ref "D104") (pin "C") (pinfunction "C_C") (pintype "passive"))
      (node (ref "D107") (pin "C") (pinfunction "C_C") (pintype "passive"))
      (node (ref "D109") (pin "C") (pinfunction "C_C") (pintype "passive"))
      (node (ref "D11") (pin "C") (pinfunction "C_C") (pintype "passive"))
      (node (ref "D112") (pin "A") (pinfunction "A_A") (pintype "passive"))
      (node (ref "D113") (pin "C") (pinfunction "C_C") (pintype "passive"))
      (node (ref "D115") (pin "C") (pinfunction "C_C") (pintype "passive"))
      (node (ref "D121") (pin "C") (pinfunction "C_C") (pintype "passive"))
      (node (ref "D124") (pin "C") (pinfunction "C_C") (pintype "passive"))
      (node (ref "D128") (pin "C") (pinfunction "C_C") (pintype "passive"))
      (node (ref "D130") (pin "C") (pinfunction "C_C") (pintype "passive"))
      (node (ref "D133") (pin "C") (pinfunction "C_C") (pintype "passive"))
      (node (ref "D22") (pin "C") (pinfunction "C_C") (pintype "passive"))
      (node (ref "D24") (pin "C") (pinfunction "C_C") (pintype "passive"))
      (node (ref "D25") (pin "C") (pinfunction "C_C") (pintype "passive"))
      (node (ref "D60") (pin "C") (pinfunction "C_C") (pintype "passive"))
      (node (ref "D75") (pin "C") (pinfunction "C_C") (pintype "passive"))
      (node (ref "D79") (pin "C") (pinfunction "C_C") (pintype "passive"))
      (node (ref "D81") (pin "C") (pinfunction "C_C") (pintype "passive"))
      (node (ref "D84") (pin "C") (pinfunction "C_C") (pintype "passive"))
      (node (ref "D90") (pin "C") (pinfunction "C_C") (pintype "passive"))
      (node (ref "D92") (pin "C") (pinfunction "C_C") (pintype "passive"))
      (node (ref "D95") (pin "C") (pinfunction "C_C") (pintype "passive"))
      (node (ref "D97") (pin "C") (pinfunction "C_C") (pintype "passive"))
    )
    (net (code "4") (name "/-3V") (class "Default")
      (node (ref "C18") (pin "2") (pinfunction "2_2") (pintype "passive"))
      (node (ref "D110") (pin "C") (pinfunction "C_C") (pintype "passive"))
      (node (ref "D122") (pin "A") (pinfunction "A_A") (pintype "passive"))
      (node (ref "D127") (pin "A") (pinfunction "A_A") (pintype "passive"))
      (node (ref "D134") (pin "A") (pinfunction "A_A") (pintype "passive"))
      (node (ref "D135") (pin "A") (pinfunction "A_A") (pintype "passive"))
      (node (ref "D136") (pin "A") (pinfunction "A_A") (pintype "passive"))
      (node (ref "D137") (pin "A") (pinfunction "A_A") (pintype "passive"))
      (node (ref "D138") (pin "A") (pinfunction "A_A") (pintype "passive"))
      (node (ref "D38") (pin "A") (pinfunction "A_A") (pintype "passive"))
      (node (ref "D48") (pin "A") (pinfunction "A_A") (pintype "passive"))
      (node (ref "D50") (pin "A") (pinfunction "A_A") (pintype "passive"))
      (node (ref "D52") (pin "A") (pinfunction "A_A") (pintype "passive"))
      (node (ref "D57") (pin "A") (pinfunction "A_A") (pintype "passive"))
      (node (ref "D61") (pin "A") (pinfunction "A_A") (pintype "passive"))
      (node (ref "D74") (pin "A") (pinfunction "A_A") (pintype "passive"))
      (node (ref "R54") (pin "2") (pinfunction "2_2") (pintype "passive"))
    )
    (net (code "5") (name "/AC") (class "Default")
      (node (ref "D106") (pin "A") (pinfunction "A_A") (pintype "passive"))
      (node (ref "D107") (pin "A") (pinfunction "A_A") (pintype "passive"))
      (node (ref "U$1") (pin "BN2") (pinfunction "1_BN2") (pintype "bidirectional"))
    )
    (net (code "6") (name "/AC2MB") (class "Default")
      (node (ref "D96") (pin "A") (pinfunction "A_A") (pintype "passive"))
      (node (ref "D97") (pin "A") (pinfunction "A_A") (pintype "passive"))
      (node (ref "U$1") (pin "BT2") (pinfunction "1_BT2") (pintype "bidirectional"))
    )
    (net (code "7") (name "/CLEAR_MA") (class "Default")
      (node (ref "D41") (pin "A") (pinfunction "A_A") (pintype "passive"))
      (node (ref "U$1") (pin "AJ2") (pinfunction "1_AJ2") (pintype "bidirectional"))
    )
    (net (code "8") (name "/CLEAR_MA2") (class "Default")
      (node (ref "D40") (pin "A") (pinfunction "A_A") (pintype "passive"))
      (node (ref "U$1") (pin "AL2") (pinfunction "1_AL2") (pintype "bidirectional"))
    )
    (net (code "9") (name "/CLEAR_MB") (class "Default")
      (node (ref "D43") (pin "A") (pinfunction "A_A") (pintype "passive"))
      (node (ref "U$1") (pin "AU2") (pinfunction "1_AU2") (pintype "bidirectional"))
    )
    (net (code "10") (name "/CLEAR_PC") (class "Default")
      (node (ref "D30") (pin "A") (pinfunction "A_A") (pintype "passive"))
      (node (ref "U$1") (pin "AV2") (pinfunction "1_AV2") (pintype "bidirectional"))
    )
    (net (code "11") (name "/COMP_PC_PULSE") (class "Default")
      (node (ref "D15") (pin "A") (pinfunction "A_A") (pintype "passive"))
      (node (ref "D60") (pin "A") (pinfunction "A_A") (pintype "passive"))
      (node (ref "D63") (pin "A") (pinfunction "A_A") (pintype "passive"))
      (node (ref "U$1") (pin "BD2") (pinfunction "1_BD2") (pintype "bidirectional"))
    )
    (net (code "12") (name "/COUNT_MB") (class "Default")
      (node (ref "D26") (pin "A") (pinfunction "A_A") (pintype "passive"))
      (node (ref "D80") (pin "A") (pinfunction "A_A") (pintype "passive"))
      (node (ref "D81") (pin "A") (pinfunction "A_A") (pintype "passive"))
      (node (ref "U$1") (pin "BJ2") (pinfunction "1_BJ2") (pintype "bidirectional"))
    )
    (net (code "13") (name "/CPC_LVL") (class "Default")
      (node (ref "D23") (pin "A") (pinfunction "A_A") (pintype "passive"))
      (node (ref "D73") (pin "A") (pinfunction "A_A") (pintype "passive"))
      (node (ref "D75") (pin "A") (pinfunction "A_A") (pintype "passive"))
      (node (ref "U$1") (pin "BE2") (pinfunction "1_BE2") (pintype "bidirectional"))
    )
    (net (code "14") (name "/DADDR2MA") (class "Default")
      (node (ref "D100") (pin "A") (pinfunction "A_A") (pintype "passive"))
      (node (ref "D103") (pin "A") (pinfunction "A_A") (pintype "passive"))
      (node (ref "D2") (pin "A") (pinfunction "A_A") (pintype "passive"))
      (node (ref "U$1") (pin "AP2") (pinfunction "1_AP2") (pintype "bidirectional"))
    )
    (net (code "15") (name "/DATA") (class "Default")
      (node (ref "D132") (pin "A") (pinfunction "A_A") (pintype "passive"))
      (node (ref "D133") (pin "A") (pinfunction "A_A") (pintype "passive"))
      (node (ref "D138") (pin "C") (pinfunction "C_C") (pintype "passive"))
      (node (ref "R63") (pin "2") (pinfunction "2_2") (pintype "passive"))
      (node (ref "U$1") (pin "BM2") (pinfunction "1_BM2") (pintype "bidirectional"))
    )
    (net (code "16") (name "/DATA2MB") (class "Default")
      (node (ref "D129") (pin "A") (pinfunction "A_A") (pintype "passive"))
      (node (ref "D130") (pin "A") (pinfunction "A_A") (pintype "passive"))
      (node (ref "U$1") (pin "BS2") (pinfunction "1_BS2") (pintype "bidirectional"))
    )
    (net (code "17") (name "/MA=0") (class "Default")
      (node (ref "C24") (pin "2") (pinfunction "2_2") (pintype "passive"))
      (node (ref "D57") (pin "C") (pinfunction "C_C") (pintype "passive"))
      (node (ref "D58") (pin "A") (pinfunction "A_A") (pintype "passive"))
      (node (ref "Q4") (pin "3") (pinfunction "C_3") (pintype "passive"))
      (node (ref "R30") (pin "2") (pinfunction "2_2") (pintype "passive"))
      (node (ref "R72") (pin "2") (pinfunction "2_2") (pintype "passive"))
    )
    (net (code "18") (name "/MA=1") (class "Default")
      (node (ref "C23") (pin "2") (pinfunction "2_2") (pintype "passive"))
      (node (ref "D48") (pin "C") (pinfunction "C_C") (pintype "passive"))
      (node (ref "D49") (pin "A") (pinfunction "A_A") (pintype "passive"))
      (node (ref "Q6") (pin "3") (pinfunction "C_3") (pintype "passive"))
      (node (ref "R26") (pin "2") (pinfunction "2_2") (pintype "passive"))
      (node (ref "R66") (pin "2") (pinfunction "2_2") (pintype "passive"))
    )
    (net (code "19") (name "/MAOUT0") (class "Default")
      (node (ref "D127") (pin "C") (pinfunction "C_C") (pintype "passive"))
      (node (ref "Q10") (pin "3") (pinfunction "C_3") (pintype "passive"))
      (node (ref "R65") (pin "2") (pinfunction "2_2") (pintype "passive"))
      (node (ref "U$1") (pin "AE2") (pinfunction "1_AE2") (pintype "bidirectional"))
    )
    (net (code "20") (name "/MAOUT1") (class "Default")
      (node (ref "D134") (pin "C") (pinfunction "C_C") (pintype "passive"))
      (node (ref "Q11") (pin "3") (pinfunction "C_3") (pintype "passive"))
      (node (ref "R71") (pin "2") (pinfunction "2_2") (pintype "passive"))
      (node (ref "U$1") (pin "AH2") (pinfunction "1_AH2") (pintype "bidirectional"))
    )
    (net (code "21") (name "/MB2MA") (class "Default")
      (node (ref "D14") (pin "A") (pinfunction "A_A") (pintype "passive"))
      (node (ref "D89") (pin "A") (pinfunction "A_A") (pintype "passive"))
      (node (ref "D90") (pin "A") (pinfunction "A_A") (pintype "passive"))
      (node (ref "U$1") (pin "AN2") (pinfunction "1_AN2") (pintype "bidirectional"))
    )
    (net (code "22") (name "/MB2PC") (class "Default")
      (node (ref "D3") (pin "A") (pinfunction "A_A") (pintype "passive"))
      (node (ref "D77") (pin "A") (pinfunction "A_A") (pintype "passive"))
      (node (ref "D84") (pin "A") (pinfunction "A_A") (pintype "passive"))
      (node (ref "U$1") (pin "BA2") (pinfunction "1_BA2") (pintype "bidirectional"))
    )
    (net (code "23") (name "/MB=0") (class "Default")
      (node (ref "C21") (pin "2") (pinfunction "2_2") (pintype "passive"))
      (node (ref "D61") (pin "C") (pinfunction "C_C") (pintype "passive"))
      (node (ref "D62") (pin "A") (pinfunction "A_A") (pintype "passive"))
      (node (ref "D78") (pin "A") (pinfunction "A_A") (pintype "passive"))
      (node (ref "D87") (pin "A") (pinfunction "A_A") (pintype "passive"))
      (node (ref "D95") (pin "A") (pinfunction "A_A") (pintype "passive"))
      (node (ref "D98") (pin "A") (pinfunction "A_A") (pintype "passive"))
      (node (ref "Q5") (pin "3") (pinfunction "C_3") (pintype "passive"))
      (node (ref "R31") (pin "2") (pinfunction "2_2") (pintype "passive"))
      (node (ref "R70") (pin "2") (pinfunction "2_2") (pintype "passive"))
    )
    (net (code "24") (name "/MB=1") (class "Default")
      (node (ref "C22") (pin "2") (pinfunction "2_2") (pintype "passive"))
      (node (ref "D21") (pin "A") (pinfunction "A_A") (pintype "passive"))
      (node (ref "D22") (pin "A") (pinfunction "A_A") (pintype "passive"))
      (node (ref "D27") (pin "A") (pinfunction "A_A") (pintype "passive"))
      (node (ref "D52") (pin "C") (pinfunction "C_C") (pintype "passive"))
      (node (ref "D53") (pin "A") (pinfunction "A_A") (pintype "passive"))
      (node (ref "D9") (pin "A") (pinfunction "A_A") (pintype "passive"))
      (node (ref "Q7") (pin "3") (pinfunction "C_3") (pintype "passive"))
      (node (ref "R29") (pin "2") (pinfunction "2_2") (pintype "passive"))
      (node (ref "R74") (pin "2") (pinfunction "2_2") (pintype "passive"))
    )
    (net (code "25") (name "/MBCARRYENA") (class "Default")
      (node (ref "D25") (pin "A") (pinfunction "A_A") (pintype "passive"))
      (node (ref "D36") (pin "A") (pinfunction "A_A") (pintype "passive"))
      (node (ref "D88") (pin "A") (pinfunction "A_A") (pintype "passive"))
      (node (ref "U$1") (pin "BH2") (pinfunction "1_BH2") (pintype "bidirectional"))
    )
    (net (code "26") (name "/MBOUT0") (class "Default")
      (node (ref "D136") (pin "C") (pinfunction "C_C") (pintype "passive"))
      (node (ref "Q13") (pin "3") (pinfunction "C_3") (pintype "passive"))
      (node (ref "R75") (pin "2") (pinfunction "2_2") (pintype "passive"))
      (node (ref "U$1") (pin "AD2") (pinfunction "1_AD2") (pintype "bidirectional"))
    )
    (net (code "27") (name "/MBOUT1") (class "Default")
      (node (ref "D135") (pin "C") (pinfunction "C_C") (pintype "passive"))
      (node (ref "Q12") (pin "3") (pinfunction "C_3") (pintype "passive"))
      (node (ref "R73") (pin "2") (pinfunction "2_2") (pintype "passive"))
      (node (ref "U$1") (pin "AF2") (pinfunction "1_AF2") (pintype "bidirectional"))
    )
    (net (code "28") (name "/PC2MA") (class "Default")
      (node (ref "D29") (pin "A") (pinfunction "A_A") (pintype "passive"))
      (node (ref "D76") (pin "A") (pinfunction "A_A") (pintype "passive"))
      (node (ref "D79") (pin "A") (pinfunction "A_A") (pintype "passive"))
      (node (ref "U$1") (pin "AM2") (pinfunction "1_AM2") (pintype "bidirectional"))
    )
    (net (code "29") (name "/PC2MB") (class "Default")
      (node (ref "D114") (pin "A") (pinfunction "A_A") (pintype "passive"))
      (node (ref "D115") (pin "A") (pinfunction "A_A") (pintype "passive"))
      (node (ref "D12") (pin "A") (pinfunction "A_A") (pintype "passive"))
      (node (ref "U$1") (pin "BV2") (pinfunction "1_BV2") (pintype "bidirectional"))
    )
    (net (code "30") (name "/PC=0") (class "Default")
      (node (ref "D120") (pin "A") (pinfunction "A_A") (pintype "passive"))
      (node (ref "D121") (pin "A") (pinfunction "A_A") (pintype "passive"))
      (node (ref "D50") (pin "C") (pinfunction "C_C") (pintype "passive"))
      (node (ref "D51") (pin "A") (pinfunction "A_A") (pintype "passive"))
      (node (ref "D59") (pin "A") (pinfunction "A_A") (pintype "passive"))
      (node (ref "D86") (pin "A") (pinfunction "A_A") (pintype "passive"))
      (node (ref "Q2") (pin "3") (pinfunction "C_3") (pintype "passive"))
      (node (ref "R23") (pin "2") (pinfunction "2_2") (pintype "passive"))
      (node (ref "U$1") (pin "BL2") (pinfunction "1_BL2") (pintype "bidirectional"))
    )
    (net (code "31") (name "/PC=1") (class "Default")
      (node (ref "D13") (pin "A") (pinfunction "A_A") (pintype "passive"))
      (node (ref "D18") (pin "A") (pinfunction "A_A") (pintype "passive"))
      (node (ref "D24") (pin "A") (pinfunction "A_A") (pintype "passive"))
      (node (ref "D37") (pin "A") (pinfunction "A_A") (pintype "passive"))
      (node (ref "D38") (pin "C") (pinfunction "C_C") (pintype "passive"))
      (node (ref "D39") (pin "A") (pinfunction "A_A") (pintype "passive"))
      (node (ref "Q3") (pin "3") (pinfunction "C_3") (pintype "passive"))
      (node (ref "R20") (pin "2") (pinfunction "2_2") (pintype "passive"))
      (node (ref "U$1") (pin "BK2") (pinfunction "1_BK2") (pintype "bidirectional"))
    )
    (net (code "32") (name "/SET_MA") (class "Default")
      (node (ref "D69") (pin "A") (pinfunction "A_A") (pintype "passive"))
      (node (ref "U$1") (pin "AK2") (pinfunction "1_AK2") (pintype "bidirectional"))
    )
    (net (code "33") (name "/SET_MB") (class "Default")
      (node (ref "D70") (pin "A") (pinfunction "A_A") (pintype "passive"))
      (node (ref "D74") (pin "C") (pinfunction "C_C") (pintype "passive"))
      (node (ref "R38") (pin "2") (pinfunction "2_2") (pintype "passive"))
      (node (ref "U$1") (pin "AT2") (pinfunction "1_AT2") (pintype "bidirectional"))
    )
    (net (code "34") (name "/SHIFT") (class "Default")
      (node (ref "D123") (pin "A") (pinfunction "A_A") (pintype "passive"))
      (node (ref "D124") (pin "A") (pinfunction "A_A") (pintype "passive"))
      (node (ref "D4") (pin "A") (pinfunction "A_A") (pintype "passive"))
      (node (ref "U$1") (pin "BU2") (pinfunction "1_BU2") (pintype "bidirectional"))
    )
    (net (code "35") (name "/SR") (class "Default")
      (node (ref "D101") (pin "A") (pinfunction "A_A") (pintype "passive"))
      (node (ref "D104") (pin "A") (pinfunction "A_A") (pintype "passive"))
      (node (ref "U$1") (pin "BF2") (pinfunction "1_BF2") (pintype "bidirectional"))
    )
    (net (code "36") (name "/SR2PC") (class "Default")
      (node (ref "D91") (pin "A") (pinfunction "A_A") (pintype "passive"))
      (node (ref "D92") (pin "A") (pinfunction "A_A") (pintype "passive"))
      (node (ref "U$1") (pin "BB2") (pinfunction "1_BB2") (pintype "bidirectional"))
    )
    (net (code "37") (name "GND") (class "Default")
      (node (ref "C18") (pin "1") (pinfunction "1_1") (pintype "passive"))
      (node (ref "D113") (pin "A") (pinfunction "A_A") (pintype "passive"))
      (node (ref "Q10") (pin "1") (pinfunction "E_1") (pintype "passive"))
      (node (ref "Q11") (pin "1") (pinfunction "E_1") (pintype "passive"))
      (node (ref "Q12") (pin "1") (pinfunction "E_1") (pintype "passive"))
      (node (ref "Q13") (pin "1") (pinfunction "E_1") (pintype "passive"))
      (node (ref "Q2") (pin "1") (pinfunction "E_1") (pintype "passive"))
      (node (ref "Q3") (pin "1") (pinfunction "E_1") (pintype "passive"))
      (node (ref "Q4") (pin "1") (pinfunction "E_1") (pintype "passive"))
      (node (ref "Q5") (pin "1") (pinfunction "E_1") (pintype "passive"))
      (node (ref "Q6") (pin "1") (pinfunction "E_1") (pintype "passive"))
      (node (ref "Q7") (pin "1") (pinfunction "E_1") (pintype "passive"))
      (node (ref "Q9") (pin "1") (pinfunction "E_1") (pintype "passive"))
      (node (ref "U$1") (pin "AC2") (pinfunction "1_AC2") (pintype "bidirectional"))
      (node (ref "U$1") (pin "BC2") (pinfunction "1_BC2") (pintype "bidirectional"))
    )
    (net (code "38") (name "Net-(C1-Pad1)") (class "Default")
      (node (ref "C1") (pin "1") (pinfunction "1_1") (pintype "passive"))
      (node (ref "D2") (pin "C") (pinfunction "C_C") (pintype "passive"))
      (node (ref "R1") (pin "2") (pinfunction "2_2") (pintype "passive"))
    )
    (net (code "39") (name "Net-(C1-Pad2)") (class "Default")
      (node (ref "C1") (pin "2") (pinfunction "2_2") (pintype "passive"))
      (node (ref "D5") (pin "A") (pinfunction "A_A") (pintype "passive"))
      (node (ref "D8") (pin "C") (pinfunction "C_C") (pintype "passive"))
      (node (ref "R4") (pin "2") (pinfunction "2_2") (pintype "passive"))
    )
    (net (code "40") (name "Net-(C2-Pad1)") (class "Default")
      (node (ref "C2") (pin "1") (pinfunction "1_1") (pintype "passive"))
      (node (ref "D3") (pin "C") (pinfunction "C_C") (pintype "passive"))
      (node (ref "R2") (pin "2") (pinfunction "2_2") (pintype "passive"))
    )
    (net (code "41") (name "Net-(C2-Pad2)") (class "Default")
      (node (ref "C2") (pin "2") (pinfunction "2_2") (pintype "passive"))
      (node (ref "D6") (pin "A") (pinfunction "A_A") (pintype "passive"))
      (node (ref "D9") (pin "C") (pinfunction "C_C") (pintype "passive"))
      (node (ref "R5") (pin "2") (pinfunction "2_2") (pintype "passive"))
    )
    (net (code "42") (name "Net-(C3-Pad1)") (class "Default")
      (node (ref "C3") (pin "1") (pinfunction "1_1") (pintype "passive"))
      (node (ref "D4") (pin "C") (pinfunction "C_C") (pintype "passive"))
      (node (ref "R3") (pin "2") (pinfunction "2_2") (pintype "passive"))
    )
    (net (code "43") (name "Net-(C3-Pad2)") (class "Default")
      (node (ref "C3") (pin "2") (pinfunction "2_2") (pintype "passive"))
      (node (ref "D10") (pin "C") (pinfunction "C_C") (pintype "passive"))
      (node (ref "D7") (pin "A") (pinfunction "A_A") (pintype "passive"))
      (node (ref "R6") (pin "2") (pinfunction "2_2") (pintype "passive"))
    )
    (net (code "44") (name "Net-(C4-Pad1)") (class "Default")
      (node (ref "C4") (pin "1") (pinfunction "1_1") (pintype "passive"))
      (node (ref "D12") (pin "C") (pinfunction "C_C") (pintype "passive"))
      (node (ref "R7") (pin "2") (pinfunction "2_2") (pintype "passive"))
    )
    (net (code "45") (name "Net-(C4-Pad2)") (class "Default")
      (node (ref "C4") (pin "2") (pinfunction "2_2") (pintype "passive"))
      (node (ref "D16") (pin "A") (pinfunction "A_A") (pintype "passive"))
      (node (ref "D18") (pin "C") (pinfunction "C_C") (pintype "passive"))
      (node (ref "R10") (pin "2") (pinfunction "2_2") (pintype "passive"))
    )
    (net (code "46") (name "Net-(C5-Pad1)") (class "Default")
      (node (ref "C5") (pin "1") (pinfunction "1_1") (pintype "passive"))
      (node (ref "D14") (pin "C") (pinfunction "C_C") (pintype "passive"))
      (node (ref "R8") (pin "2") (pinfunction "2_2") (pintype "passive"))
    )
    (net (code "47") (name "Net-(C5-Pad2)") (class "Default")
      (node (ref "C5") (pin "2") (pinfunction "2_2") (pintype "passive"))
      (node (ref "D19") (pin "A") (pinfunction "A_A") (pintype "passive"))
      (node (ref "D21") (pin "C") (pinfunction "C_C") (pintype "passive"))
      (node (ref "R11") (pin "2") (pinfunction "2_2") (pintype "passive"))
    )
    (net (code "48") (name "Net-(C6-Pad1)") (class "Default")
      (node (ref "C6") (pin "1") (pinfunction "1_1") (pintype "passive"))
      (node (ref "D13") (pin "C") (pinfunction "C_C") (pintype "passive"))
      (node (ref "D15") (pin "C") (pinfunction "C_C") (pintype "passive"))
      (node (ref "D17") (pin "A") (pinfunction "A_A") (pintype "passive"))
      (node (ref "R9") (pin "2") (pinfunction "2_2") (pintype "passive"))
    )
    (net (code "49") (name "Net-(C6-Pad2)") (class "Default")
      (node (ref "C6") (pin "2") (pinfunction "2_2") (pintype "passive"))
      (node (ref "D17") (pin "C") (pinfunction "C_C") (pintype "passive"))
      (node (ref "D20") (pin "A") (pinfunction "A_A") (pintype "passive"))
      (node (ref "D23") (pin "C") (pinfunction "C_C") (pintype "passive"))
      (node (ref "R12") (pin "2") (pinfunction "2_2") (pintype "passive"))
    )
    (net (code "50") (name "Net-(C7-Pad1)") (class "Default")
      (node (ref "C7") (pin "1") (pinfunction "1_1") (pintype "passive"))
      (node (ref "D26") (pin "C") (pinfunction "C_C") (pintype "passive"))
      (node (ref "D27") (pin "C") (pinfunction "C_C") (pintype "passive"))
      (node (ref "D28") (pin "A") (pinfunction "A_A") (pintype "passive"))
      (node (ref "R13") (pin "2") (pinfunction "2_2") (pintype "passive"))
    )
    (net (code "51") (name "Net-(C8-Pad1)") (class "Default")
      (node (ref "C8") (pin "1") (pinfunction "1_1") (pintype "passive"))
      (node (ref "D29") (pin "C") (pinfunction "C_C") (pintype "passive"))
      (node (ref "R14") (pin "2") (pinfunction "2_2") (pintype "passive"))
    )
    (net (code "52") (name "Net-(C8-Pad2)") (class "Default")
      (node (ref "C8") (pin "2") (pinfunction "2_2") (pintype "passive"))
      (node (ref "D33") (pin "A") (pinfunction "A_A") (pintype "passive"))
      (node (ref "D37") (pin "C") (pinfunction "C_C") (pintype "passive"))
      (node (ref "R18") (pin "2") (pinfunction "2_2") (pintype "passive"))
    )
    (net (code "53") (name "Net-(C9-Pad1)") (class "Default")
      (node (ref "C9") (pin "1") (pinfunction "1_1") (pintype "passive"))
      (node (ref "D59") (pin "C") (pinfunction "C_C") (pintype "passive"))
      (node (ref "D63") (pin "C") (pinfunction "C_C") (pintype "passive"))
      (node (ref "D66") (pin "A") (pinfunction "A_A") (pintype "passive"))
      (node (ref "R32") (pin "2") (pinfunction "2_2") (pintype "passive"))
    )
    (net (code "54") (name "Net-(C9-Pad2)") (class "Default")
      (node (ref "C9") (pin "2") (pinfunction "2_2") (pintype "passive"))
      (node (ref "D66") (pin "C") (pinfunction "C_C") (pintype "passive"))
      (node (ref "D72") (pin "A") (pinfunction "A_A") (pintype "passive"))
      (node (ref "D73") (pin "C") (pinfunction "C_C") (pintype "passive"))
      (node (ref "R37") (pin "2") (pinfunction "2_2") (pintype "passive"))
    )
    (net (code "55") (name "Net-(C10-Pad1)") (class "Default")
      (node (ref "C10") (pin "1") (pinfunction "1_1") (pintype "passive"))
      (node (ref "D76") (pin "C") (pinfunction "C_C") (pintype "passive"))
      (node (ref "R39") (pin "2") (pinfunction "2_2") (pintype "passive"))
    )
    (net (code "56") (name "Net-(C10-Pad2)") (class "Default")
      (node (ref "C10") (pin "2") (pinfunction "2_2") (pintype "passive"))
      (node (ref "D82") (pin "A") (pinfunction "A_A") (pintype "passive"))
      (node (ref "D86") (pin "C") (pinfunction "C_C") (pintype "passive"))
      (node (ref "R42") (pin "2") (pinfunction "2_2") (pintype "passive"))
    )
    (net (code "57") (name "Net-(C11-Pad1)") (class "Default")
      (node (ref "C11") (pin "1") (pinfunction "1_1") (pintype "passive"))
      (node (ref "D77") (pin "C") (pinfunction "C_C") (pintype "passive"))
      (node (ref "R40") (pin "2") (pinfunction "2_2") (pintype "passive"))
    )
    (net (code "58") (name "Net-(C11-Pad2)") (class "Default")
      (node (ref "C11") (pin "2") (pinfunction "2_2") (pintype "passive"))
      (node (ref "D83") (pin "A") (pinfunction "A_A") (pintype "passive"))
      (node (ref "D87") (pin "C") (pinfunction "C_C") (pintype "passive"))
      (node (ref "R43") (pin "2") (pinfunction "2_2") (pintype "passive"))
    )
    (net (code "59") (name "Net-(C12-Pad1)") (class "Default")
      (node (ref "C12") (pin "1") (pinfunction "1_1") (pintype "passive"))
      (node (ref "D78") (pin "C") (pinfunction "C_C") (pintype "passive"))
      (node (ref "D80") (pin "C") (pinfunction "C_C") (pintype "passive"))
      (node (ref "D85") (pin "A") (pinfunction "A_A") (pintype "passive"))
      (node (ref "R41") (pin "2") (pinfunction "2_2") (pintype "passive"))
    )
    (net (code "60") (name "Net-(C13-Pad1)") (class "Default")
      (node (ref "C13") (pin "1") (pinfunction "1_1") (pintype "passive"))
      (node (ref "D89") (pin "C") (pinfunction "C_C") (pintype "passive"))
      (node (ref "R45") (pin "2") (pinfunction "2_2") (pintype "passive"))
    )
    (net (code "61") (name "Net-(C13-Pad2)") (class "Default")
      (node (ref "C13") (pin "2") (pinfunction "2_2") (pintype "passive"))
      (node (ref "D94") (pin "A") (pinfunction "A_A") (pintype "passive"))
      (node (ref "D98") (pin "C") (pinfunction "C_C") (pintype "passive"))
      (node (ref "R46") (pin "2") (pinfunction "2_2") (pintype "passive"))
    )
    (net (code "62") (name "Net-(C14-Pad1)") (class "Default")
      (node (ref "C14") (pin "1") (pinfunction "1_1") (pintype "passive"))
      (node (ref "D91") (pin "C") (pinfunction "C_C") (pintype "passive"))
      (node (ref "R47") (pin "2") (pinfunction "2_2") (pintype "passive"))
    )
    (net (code "63") (name "Net-(C14-Pad2)") (class "Default")
      (node (ref "C14") (pin "2") (pinfunction "2_2") (pintype "passive"))
      (node (ref "D101") (pin "C") (pinfunction "C_C") (pintype "passive"))
      (node (ref "D99") (pin "A") (pinfunction "A_A") (pintype "passive"))
      (node (ref "R50") (pin "2") (pinfunction "2_2") (pintype "passive"))
    )
    (net (code "64") (name "Net-(C15-Pad1)") (class "Default")
      (node (ref "C15") (pin "1") (pinfunction "1_1") (pintype "passive"))
      (node (ref "D96") (pin "C") (pinfunction "C_C") (pintype "passive"))
      (node (ref "R49") (pin "2") (pinfunction "2_2") (pintype "passive"))
    )
    (net (code "65") (name "Net-(C15-Pad2)") (class "Default")
      (node (ref "C15") (pin "2") (pinfunction "2_2") (pintype "passive"))
      (node (ref "D102") (pin "A") (pinfunction "A_A") (pintype "passive"))
      (node (ref "D106") (pin "C") (pinfunction "C_C") (pintype "passive"))
      (node (ref "R52") (pin "2") (pinfunction "2_2") (pintype "passive"))
    )
    (net (code "66") (name "Net-(C16-Pad1)") (class "Default")
      (node (ref "C16") (pin "1") (pinfunction "1_1") (pintype "passive"))
      (node (ref "D100") (pin "C") (pinfunction "C_C") (pintype "passive"))
      (node (ref "R51") (pin "2") (pinfunction "2_2") (pintype "passive"))
    )
    (net (code "67") (name "Net-(C16-Pad2)") (class "Default")
      (node (ref "C16") (pin "2") (pinfunction "2_2") (pintype "passive"))
      (node (ref "D105") (pin "A") (pinfunction "A_A") (pintype "passive"))
      (node (ref "D108") (pin "C") (pinfunction "C_C") (pintype "passive"))
      (node (ref "R53") (pin "2") (pinfunction "2_2") (pintype "passive"))
    )
    (net (code "68") (name "Net-(C17-Pad1)") (class "Default")
      (node (ref "C17") (pin "1") (pinfunction "1_1") (pintype "passive"))
      (node (ref "D114") (pin "C") (pinfunction "C_C") (pintype "passive"))
      (node (ref "R55") (pin "2") (pinfunction "2_2") (pintype "passive"))
    )
    (net (code "69") (name "Net-(C17-Pad2)") (class "Default")
      (node (ref "C17") (pin "2") (pinfunction "2_2") (pintype "passive"))
      (node (ref "D117") (pin "A") (pinfunction "A_A") (pintype "passive"))
      (node (ref "D120") (pin "C") (pinfunction "C_C") (pintype "passive"))
      (node (ref "R56") (pin "2") (pinfunction "2_2") (pintype "passive"))
    )
    (net (code "70") (name "Net-(C19-Pad1)") (class "Default")
      (node (ref "C19") (pin "1") (pinfunction "1_1") (pintype "passive"))
      (node (ref "D123") (pin "C") (pinfunction "C_C") (pintype "passive"))
      (node (ref "R60") (pin "2") (pinfunction "2_2") (pintype "passive"))
    )
    (net (code "71") (name "Net-(C19-Pad2)") (class "Default")
      (node (ref "C19") (pin "2") (pinfunction "2_2") (pintype "passive"))
      (node (ref "D125") (pin "A") (pinfunction "A_A") (pintype "passive"))
      (node (ref "D126") (pin "C") (pinfunction "C_C") (pintype "passive"))
      (node (ref "R62") (pin "2") (pinfunction "2_2") (pintype "passive"))
    )
    (net (code "72") (name "Net-(C20-Pad1)") (class "Default")
      (node (ref "C20") (pin "1") (pinfunction "1_1") (pintype "passive"))
      (node (ref "D129") (pin "C") (pinfunction "C_C") (pintype "passive"))
      (node (ref "R64") (pin "2") (pinfunction "2_2") (pintype "passive"))
    )
    (net (code "73") (name "Net-(C20-Pad2)") (class "Default")
      (node (ref "C20") (pin "2") (pinfunction "2_2") (pintype "passive"))
      (node (ref "D131") (pin "A") (pinfunction "A_A") (pintype "passive"))
      (node (ref "D132") (pin "C") (pinfunction "C_C") (pintype "passive"))
      (node (ref "R67") (pin "2") (pinfunction "2_2") (pintype "passive"))
    )
    (net (code "74") (name "Net-(D16-PadC)") (class "Default")
      (node (ref "D16") (pin "C") (pinfunction "C_C") (pintype "passive"))
      (node (ref "D32") (pin "A") (pinfunction "A_A") (pintype "passive"))
      (node (ref "D7") (pin "C") (pinfunction "C_C") (pintype "passive"))
    )
    (net (code "75") (name "Net-(D19-PadC)") (class "Default")
      (node (ref "D19") (pin "C") (pinfunction "C_C") (pintype "passive"))
      (node (ref "D33") (pin "C") (pinfunction "C_C") (pintype "passive"))
      (node (ref "D42") (pin "A") (pinfunction "A_A") (pintype "passive"))
      (node (ref "D5") (pin "C") (pinfunction "C_C") (pintype "passive"))
    )
    (net (code "76") (name "Net-(D20-PadC)") (class "Default")
      (node (ref "D20") (pin "C") (pinfunction "C_C") (pintype "passive"))
      (node (ref "D31") (pin "A") (pinfunction "A_A") (pintype "passive"))
      (node (ref "D6") (pin "C") (pinfunction "C_C") (pintype "passive"))
    )
    (net (code "77") (name "Net-(D30-PadC)") (class "Default")
      (node (ref "D30") (pin "C") (pinfunction "C_C") (pintype "passive"))
      (node (ref "D34") (pin "C") (pinfunction "C_C") (pintype "passive"))
      (node (ref "D39") (pin "C") (pinfunction "C_C") (pintype "passive"))
      (node (ref "R16") (pin "2") (pinfunction "2_2") (pintype "passive"))
    )
    (net (code "78") (name "Net-(D34-PadA)") (class "Default")
      (node (ref "D34") (pin "A") (pinfunction "A_A") (pintype "passive"))
      (node (ref "D35") (pin "C") (pinfunction "C_C") (pintype "passive"))
    )
    (net (code "79") (name "Net-(D40-PadC)") (class "Default")
      (node (ref "D40") (pin "C") (pinfunction "C_C") (pintype "passive"))
      (node (ref "D41") (pin "C") (pinfunction "C_C") (pintype "passive"))
      (node (ref "D44") (pin "C") (pinfunction "C_C") (pintype "passive"))
      (node (ref "D49") (pin "C") (pinfunction "C_C") (pintype "passive"))
      (node (ref "R21") (pin "2") (pinfunction "2_2") (pintype "passive"))
    )
    (net (code "80") (name "Net-(D43-PadC)") (class "Default")
      (node (ref "D43") (pin "C") (pinfunction "C_C") (pintype "passive"))
      (node (ref "D46") (pin "C") (pinfunction "C_C") (pintype "passive"))
      (node (ref "D53") (pin "C") (pinfunction "C_C") (pintype "passive"))
      (node (ref "R24") (pin "2") (pinfunction "2_2") (pintype "passive"))
    )
    (net (code "81") (name "Net-(D44-PadA)") (class "Default")
      (node (ref "D44") (pin "A") (pinfunction "A_A") (pintype "passive"))
      (node (ref "D45") (pin "C") (pinfunction "C_C") (pintype "passive"))
    )
    (net (code "82") (name "Net-(D46-PadA)") (class "Default")
      (node (ref "D46") (pin "A") (pinfunction "A_A") (pintype "passive"))
      (node (ref "D47") (pin "C") (pinfunction "C_C") (pintype "passive"))
    )
    (net (code "83") (name "Net-(D51-PadC)") (class "Default")
      (node (ref "D51") (pin "C") (pinfunction "C_C") (pintype "passive"))
      (node (ref "D54") (pin "C") (pinfunction "C_C") (pintype "passive"))
      (node (ref "R27") (pin "2") (pinfunction "2_2") (pintype "passive"))
    )
    (net (code "84") (name "Net-(D54-PadA)") (class "Default")
      (node (ref "D54") (pin "A") (pinfunction "A_A") (pintype "passive"))
      (node (ref "D55") (pin "C") (pinfunction "C_C") (pintype "passive"))
    )
    (net (code "85") (name "Net-(D56-PadA)") (class "Default")
      (node (ref "D56") (pin "A") (pinfunction "A_A") (pintype "passive"))
      (node (ref "D72") (pin "C") (pinfunction "C_C") (pintype "passive"))
      (node (ref "D83") (pin "C") (pinfunction "C_C") (pintype "passive"))
      (node (ref "D99") (pin "C") (pinfunction "C_C") (pintype "passive"))
    )
    (net (code "86") (name "Net-(D58-PadC)") (class "Default")
      (node (ref "D58") (pin "C") (pinfunction "C_C") (pintype "passive"))
      (node (ref "D64") (pin "C") (pinfunction "C_C") (pintype "passive"))
      (node (ref "D69") (pin "C") (pinfunction "C_C") (pintype "passive"))
      (node (ref "R33") (pin "2") (pinfunction "2_2") (pintype "passive"))
    )
    (net (code "87") (name "Net-(D62-PadC)") (class "Default")
      (node (ref "D62") (pin "C") (pinfunction "C_C") (pintype "passive"))
      (node (ref "D67") (pin "C") (pinfunction "C_C") (pintype "passive"))
      (node (ref "D70") (pin "C") (pinfunction "C_C") (pintype "passive"))
      (node (ref "R35") (pin "2") (pinfunction "2_2") (pintype "passive"))
    )
    (net (code "88") (name "Net-(D64-PadA)") (class "Default")
      (node (ref "D64") (pin "A") (pinfunction "A_A") (pintype "passive"))
      (node (ref "D65") (pin "C") (pinfunction "C_C") (pintype "passive"))
    )
    (net (code "89") (name "Net-(D67-PadA)") (class "Default")
      (node (ref "D67") (pin "A") (pinfunction "A_A") (pintype "passive"))
      (node (ref "D68") (pin "C") (pinfunction "C_C") (pintype "passive"))
    )
    (net (code "90") (name "Net-(D102-PadC)") (class "Default")
      (node (ref "D102") (pin "C") (pinfunction "C_C") (pintype "passive"))
      (node (ref "D117") (pin "C") (pinfunction "C_C") (pintype "passive"))
      (node (ref "D125") (pin "C") (pinfunction "C_C") (pintype "passive"))
      (node (ref "D131") (pin "C") (pinfunction "C_C") (pintype "passive"))
      (node (ref "D93") (pin "A") (pinfunction "A_A") (pintype "passive"))
    )
    (net (code "91") (name "Net-(D105-PadC)") (class "Default")
      (node (ref "D105") (pin "C") (pinfunction "C_C") (pintype "passive"))
      (node (ref "D71") (pin "A") (pinfunction "A_A") (pintype "passive"))
      (node (ref "D82") (pin "C") (pinfunction "C_C") (pintype "passive"))
      (node (ref "D94") (pin "C") (pinfunction "C_C") (pintype "passive"))
    )
    (net (code "92") (name "Net-(D110-PadA)") (class "Default")
      (node (ref "D110") (pin "A") (pinfunction "A_A") (pintype "passive"))
      (node (ref "D111") (pin "C") (pinfunction "C_C") (pintype "passive"))
    )
    (net (code "93") (name "Net-(D111-PadA)") (class "Default")
      (node (ref "D111") (pin "A") (pinfunction "A_A") (pintype "passive"))
      (node (ref "D112") (pin "C") (pinfunction "C_C") (pintype "passive"))
    )
    (net (code "94") (name "Net-(D116-PadC)") (class "Default")
      (node (ref "D116") (pin "C") (pinfunction "C_C") (pintype "passive"))
      (node (ref "D118") (pin "C") (pinfunction "C_C") (pintype "passive"))
      (node (ref "R57") (pin "2") (pinfunction "2_2") (pintype "passive"))
    )
    (net (code "95") (name "Net-(D118-PadA)") (class "Default")
      (node (ref "D118") (pin "A") (pinfunction "A_A") (pintype "passive"))
      (node (ref "D119") (pin "C") (pinfunction "C_C") (pintype "passive"))
    )
    (net (code "96") (name "Net-(Q1-B)") (class "Default")
      (node (ref "C7") (pin "2") (pinfunction "2_2") (pintype "passive"))
      (node (ref "D28") (pin "C") (pinfunction "C_C") (pintype "passive"))
      (node (ref "D36") (pin "C") (pinfunction "C_C") (pintype "passive"))
      (node (ref "Q1") (pin "2") (pinfunction "B_2") (pintype "passive"))
      (node (ref "R15") (pin "2") (pinfunction "2_2") (pintype "passive"))
    )
    (net (code "97") (name "Net-(Q1-C)") (class "Default")
      (node (ref "Q1") (pin "3") (pinfunction "C_3") (pintype "passive"))
      (node (ref "R19") (pin "1") (pinfunction "1_1") (pintype "passive"))
    )
    (net (code "98") (name "Net-(Q1-E)") (class "Default")
      (node (ref "D32") (pin "C") (pinfunction "C_C") (pintype "passive"))
      (node (ref "D47") (pin "A") (pinfunction "A_A") (pintype "passive"))
      (node (ref "Q1") (pin "1") (pinfunction "E_1") (pintype "passive"))
      (node (ref "Q5") (pin "2") (pinfunction "B_2") (pintype "passive"))
      (node (ref "R25") (pin "1") (pinfunction "1_1") (pintype "passive"))
    )
    (net (code "99") (name "Net-(Q2-B)") (class "Default")
      (node (ref "D31") (pin "C") (pinfunction "C_C") (pintype "passive"))
      (node (ref "D35") (pin "A") (pinfunction "A_A") (pintype "passive"))
      (node (ref "Q2") (pin "2") (pinfunction "B_2") (pintype "passive"))
      (node (ref "R17") (pin "1") (pinfunction "1_1") (pintype "passive"))
    )
    (net (code "100") (name "Net-(Q3-B)") (class "Default")
      (node (ref "D55") (pin "A") (pinfunction "A_A") (pintype "passive"))
      (node (ref "D56") (pin "C") (pinfunction "C_C") (pintype "passive"))
      (node (ref "Q3") (pin "2") (pinfunction "B_2") (pintype "passive"))
      (node (ref "R28") (pin "1") (pinfunction "1_1") (pintype "passive"))
    )
    (net (code "101") (name "Net-(Q4-B)") (class "Default")
      (node (ref "D42") (pin "C") (pinfunction "C_C") (pintype "passive"))
      (node (ref "D45") (pin "A") (pinfunction "A_A") (pintype "passive"))
      (node (ref "Q4") (pin "2") (pinfunction "B_2") (pintype "passive"))
      (node (ref "R22") (pin "1") (pinfunction "1_1") (pintype "passive"))
    )
    (net (code "102") (name "Net-(Q6-B)") (class "Default")
      (node (ref "D65") (pin "A") (pinfunction "A_A") (pintype "passive"))
      (node (ref "D71") (pin "C") (pinfunction "C_C") (pintype "passive"))
      (node (ref "Q6") (pin "2") (pinfunction "B_2") (pintype "passive"))
      (node (ref "R34") (pin "1") (pinfunction "1_1") (pintype "passive"))
    )
    (net (code "103") (name "Net-(Q7-B)") (class "Default")
      (node (ref "D68") (pin "A") (pinfunction "A_A") (pintype "passive"))
      (node (ref "D93") (pin "C") (pinfunction "C_C") (pintype "passive"))
      (node (ref "Q7") (pin "2") (pinfunction "B_2") (pintype "passive"))
      (node (ref "Q8") (pin "1") (pinfunction "E_1") (pintype "passive"))
      (node (ref "R36") (pin "1") (pinfunction "1_1") (pintype "passive"))
    )
    (net (code "104") (name "Net-(Q8-B)") (class "Default")
      (node (ref "C12") (pin "2") (pinfunction "2_2") (pintype "passive"))
      (node (ref "D85") (pin "C") (pinfunction "C_C") (pintype "passive"))
      (node (ref "D88") (pin "C") (pinfunction "C_C") (pintype "passive"))
      (node (ref "Q8") (pin "2") (pinfunction "B_2") (pintype "passive"))
      (node (ref "R44") (pin "2") (pinfunction "2_2") (pintype "passive"))
    )
    (net (code "105") (name "Net-(Q8-C)") (class "Default")
      (node (ref "Q8") (pin "3") (pinfunction "C_3") (pintype "passive"))
      (node (ref "R48") (pin "2") (pinfunction "2_2") (pintype "passive"))
    )
    (net (code "106") (name "Net-(Q9-B)") (class "Default")
      (node (ref "D119") (pin "A") (pinfunction "A_A") (pintype "passive"))
      (node (ref "Q9") (pin "2") (pinfunction "B_2") (pintype "passive"))
      (node (ref "R58") (pin "1") (pinfunction "1_1") (pintype "passive"))
    )
    (net (code "107") (name "Net-(Q9-C)") (class "Default")
      (node (ref "D11") (pin "A") (pinfunction "A_A") (pintype "passive"))
      (node (ref "D122") (pin "C") (pinfunction "C_C") (pintype "passive"))
      (node (ref "D8") (pin "A") (pinfunction "A_A") (pintype "passive"))
      (node (ref "Q9") (pin "3") (pinfunction "C_3") (pintype "passive"))
      (node (ref "R59") (pin "2") (pinfunction "2_2") (pintype "passive"))
    )
    (net (code "108") (name "Net-(Q10-B)") (class "Default")
      (node (ref "C23") (pin "1") (pinfunction "1_1") (pintype "passive"))
      (node (ref "Q10") (pin "2") (pinfunction "B_2") (pintype "passive"))
      (node (ref "R66") (pin "1") (pinfunction "1_1") (pintype "passive"))
    )
    (net (code "109") (name "Net-(Q11-B)") (class "Default")
      (node (ref "C24") (pin "1") (pinfunction "1_1") (pintype "passive"))
      (node (ref "Q11") (pin "2") (pinfunction "B_2") (pintype "passive"))
      (node (ref "R72") (pin "1") (pinfunction "1_1") (pintype "passive"))
    )
    (net (code "110") (name "Net-(Q12-B)") (class "Default")
      (node (ref "C21") (pin "1") (pinfunction "1_1") (pintype "passive"))
      (node (ref "Q12") (pin "2") (pinfunction "B_2") (pintype "passive"))
      (node (ref "R70") (pin "1") (pinfunction "1_1") (pintype "passive"))
    )
    (net (code "111") (name "Net-(Q13-B)") (class "Default")
      (node (ref "C22") (pin "1") (pinfunction "1_1") (pintype "passive"))
      (node (ref "Q13") (pin "2") (pinfunction "B_2") (pintype "passive"))
      (node (ref "R74") (pin "1") (pinfunction "1_1") (pintype "passive"))
    )
    (net (code "112") (name "Net-(U$1AB-1)") (class "Default")
      (node (ref "D108") (pin "A") (pinfunction "A_A") (pintype "passive"))
      (node (ref "D109") (pin "A") (pinfunction "A_A") (pintype "passive"))
      (node (ref "D116") (pin "A") (pinfunction "A_A") (pintype "passive"))
      (node (ref "D137") (pin "C") (pinfunction "C_C") (pintype "passive"))
      (node (ref "R61") (pin "2") (pinfunction "2_2") (pintype "passive"))
      (node (ref "U$1") (pin "AR2") (pinfunction "1_AR2") (pintype "bidirectional"))
    )
    (net (code "113") (name "Net-(U$1BJ-1)") (class "Default")
      (node (ref "D126") (pin "A") (pinfunction "A_A") (pintype "passive"))
      (node (ref "D128") (pin "A") (pinfunction "A_A") (pintype "passive"))
      (node (ref "U$1") (pin "BP2") (pinfunction "1_BP2") (pintype "bidirectional"))
    )
    (net (code "114") (name "Net-(U$1BL-1)") (class "Default")
      (node (ref "D1") (pin "A") (pinfunction "A_A") (pintype "passive"))
      (node (ref "D10") (pin "A") (pinfunction "A_A") (pintype "passive"))
      (node (ref "U$1") (pin "BR2") (pinfunction "1_BR2") (pintype "bidirectional"))
    )
    (net (code "115") (name "unconnected-(D139-PadA)") (class "Default")
      (node (ref "D139") (pin "A") (pinfunction "A_A") (pintype "passive"))
    )
    (net (code "116") (name "unconnected-(D139-PadC)") (class "Default")
      (node (ref "D139") (pin "C") (pinfunction "C_C") (pintype "passive"))
    )
    (net (code "117") (name "unconnected-(D140-PadA)") (class "Default")
      (node (ref "D140") (pin "A") (pinfunction "A_A") (pintype "passive"))
    )
    (net (code "118") (name "unconnected-(D140-PadC)") (class "Default")
      (node (ref "D140") (pin "C") (pinfunction "C_C") (pintype "passive"))
    )
  )
)
